# 2020.net
KiCad netlist of a schematic drawn in Altium Designer
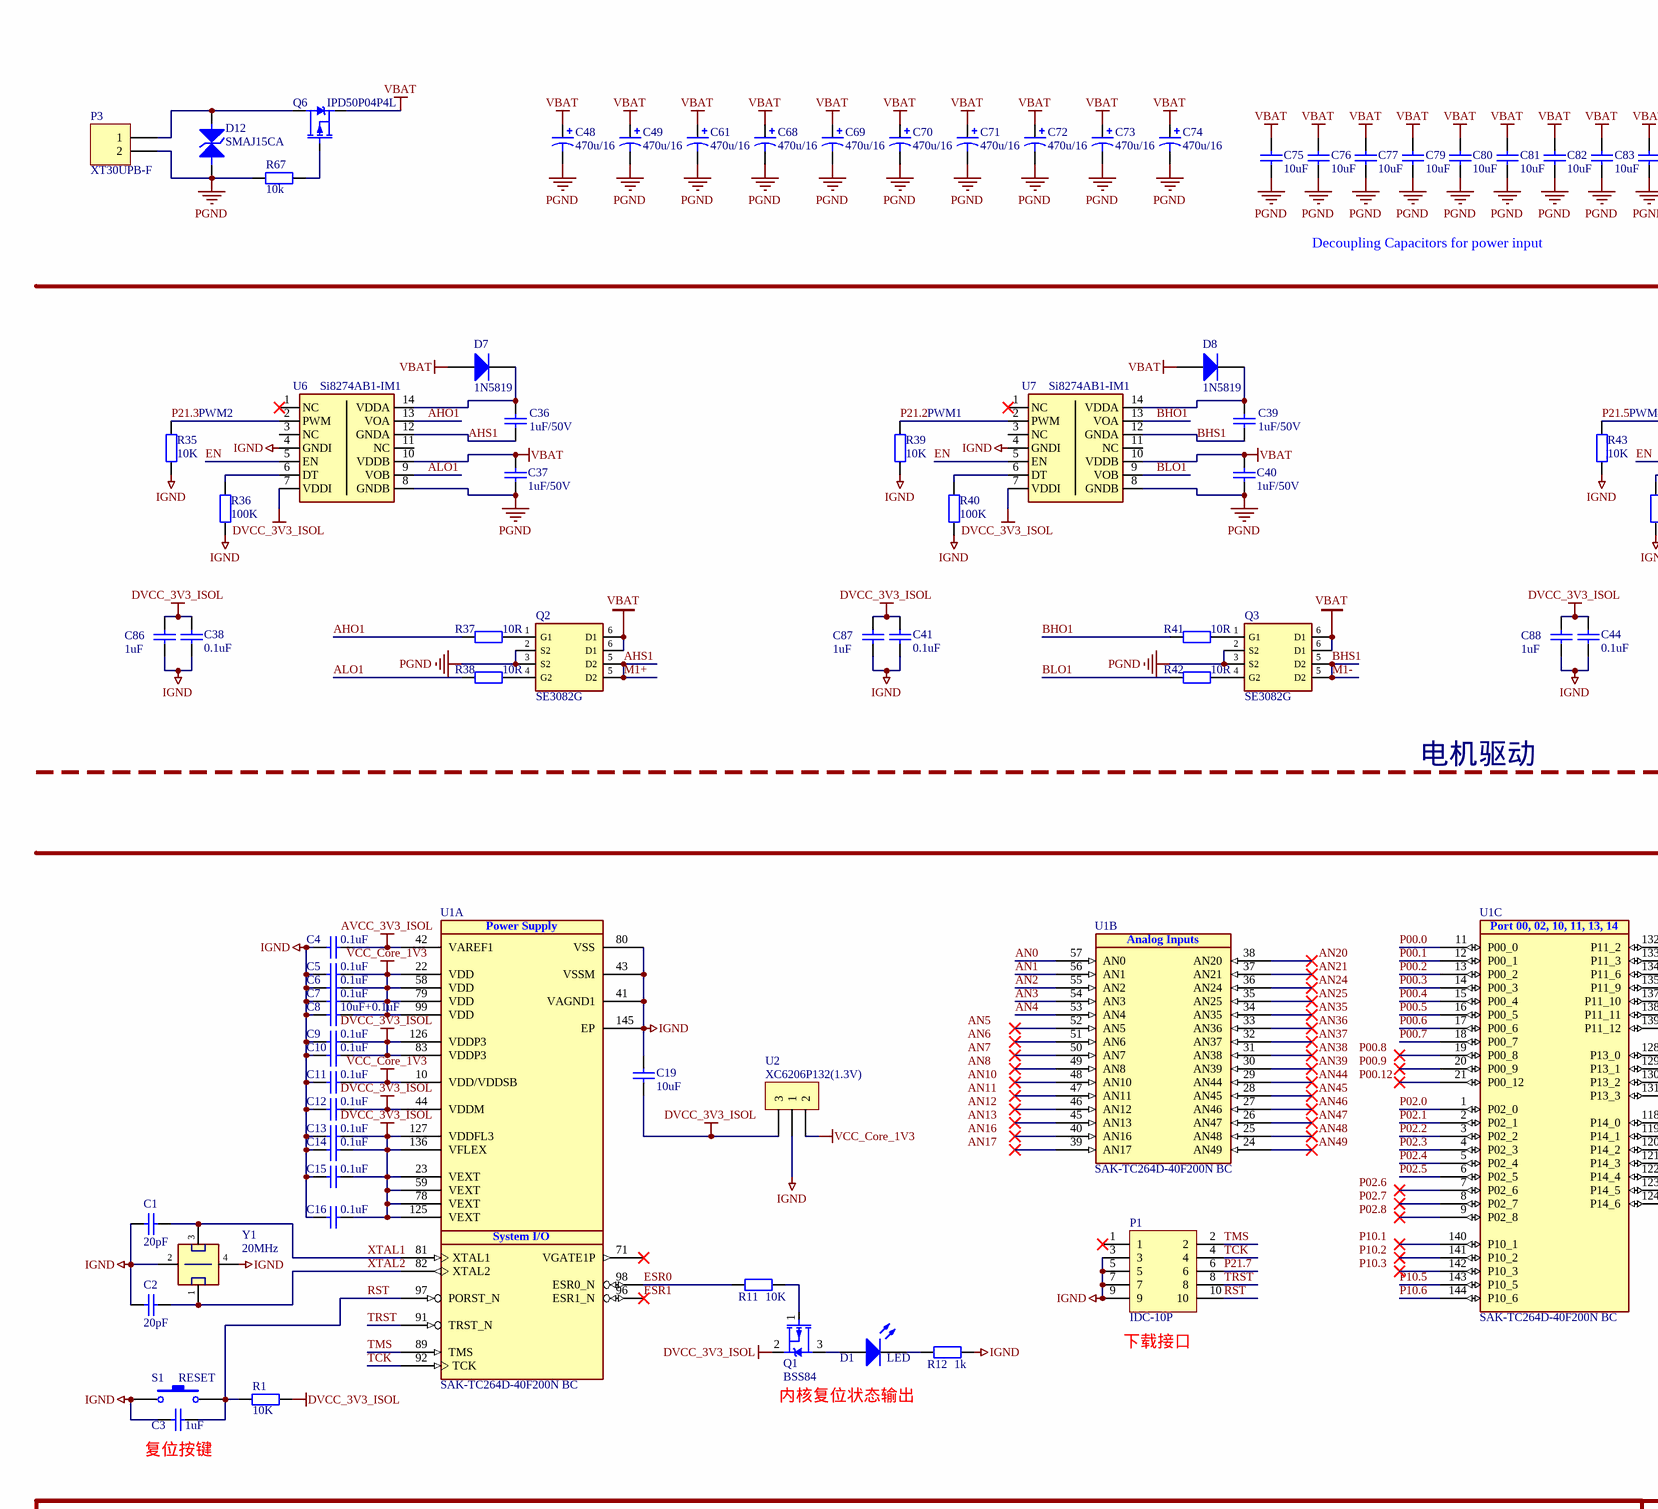
[diagram p0: 2020智能车.SchDoc, top left]
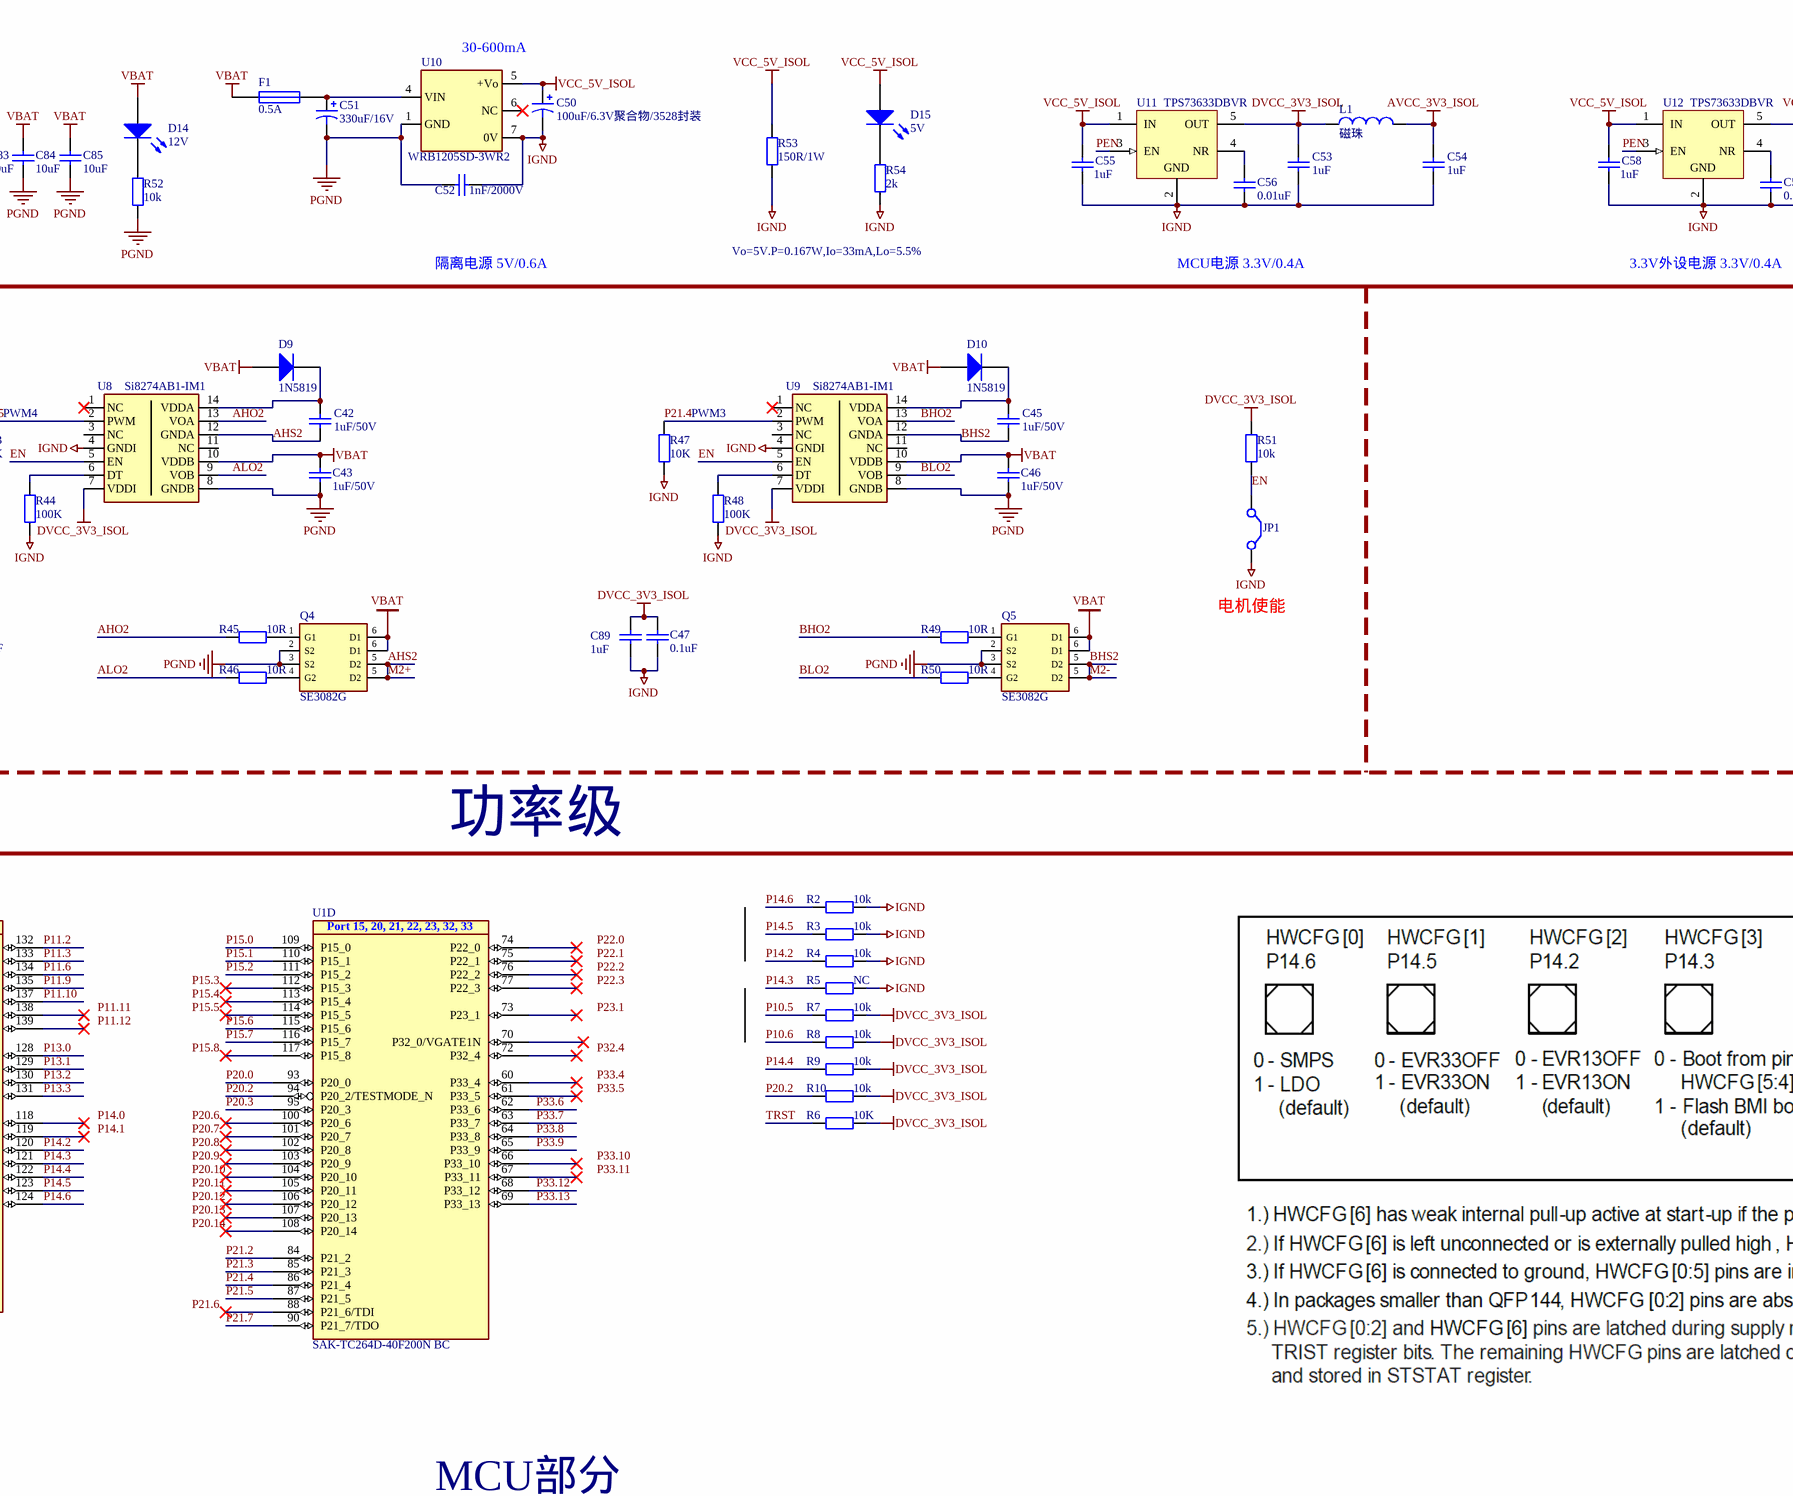
[diagram p1: 2020智能车.SchDoc, top middle]
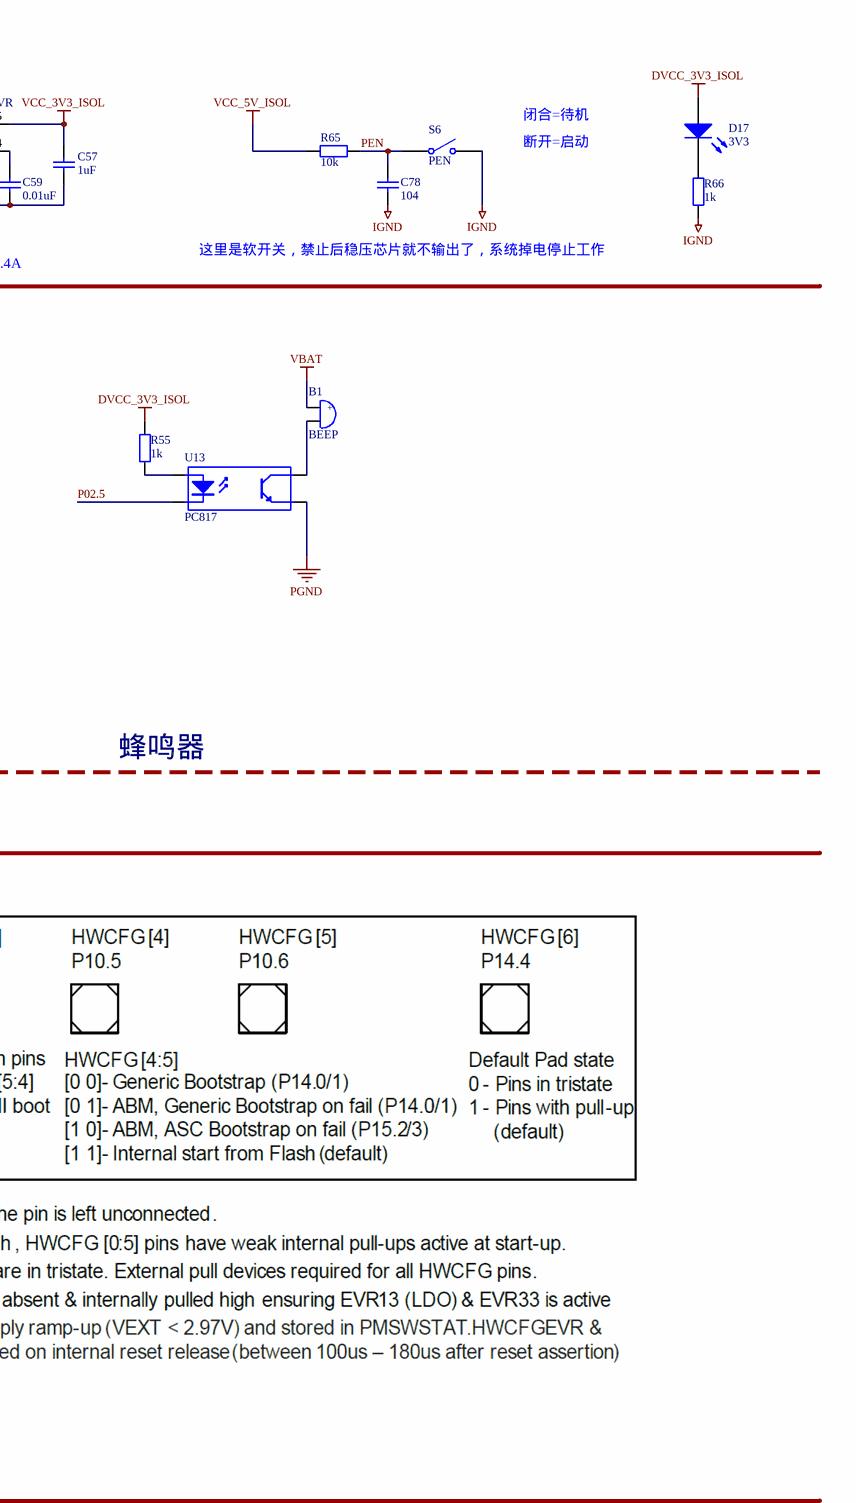
[diagram p2: 2020智能车.SchDoc, top right]
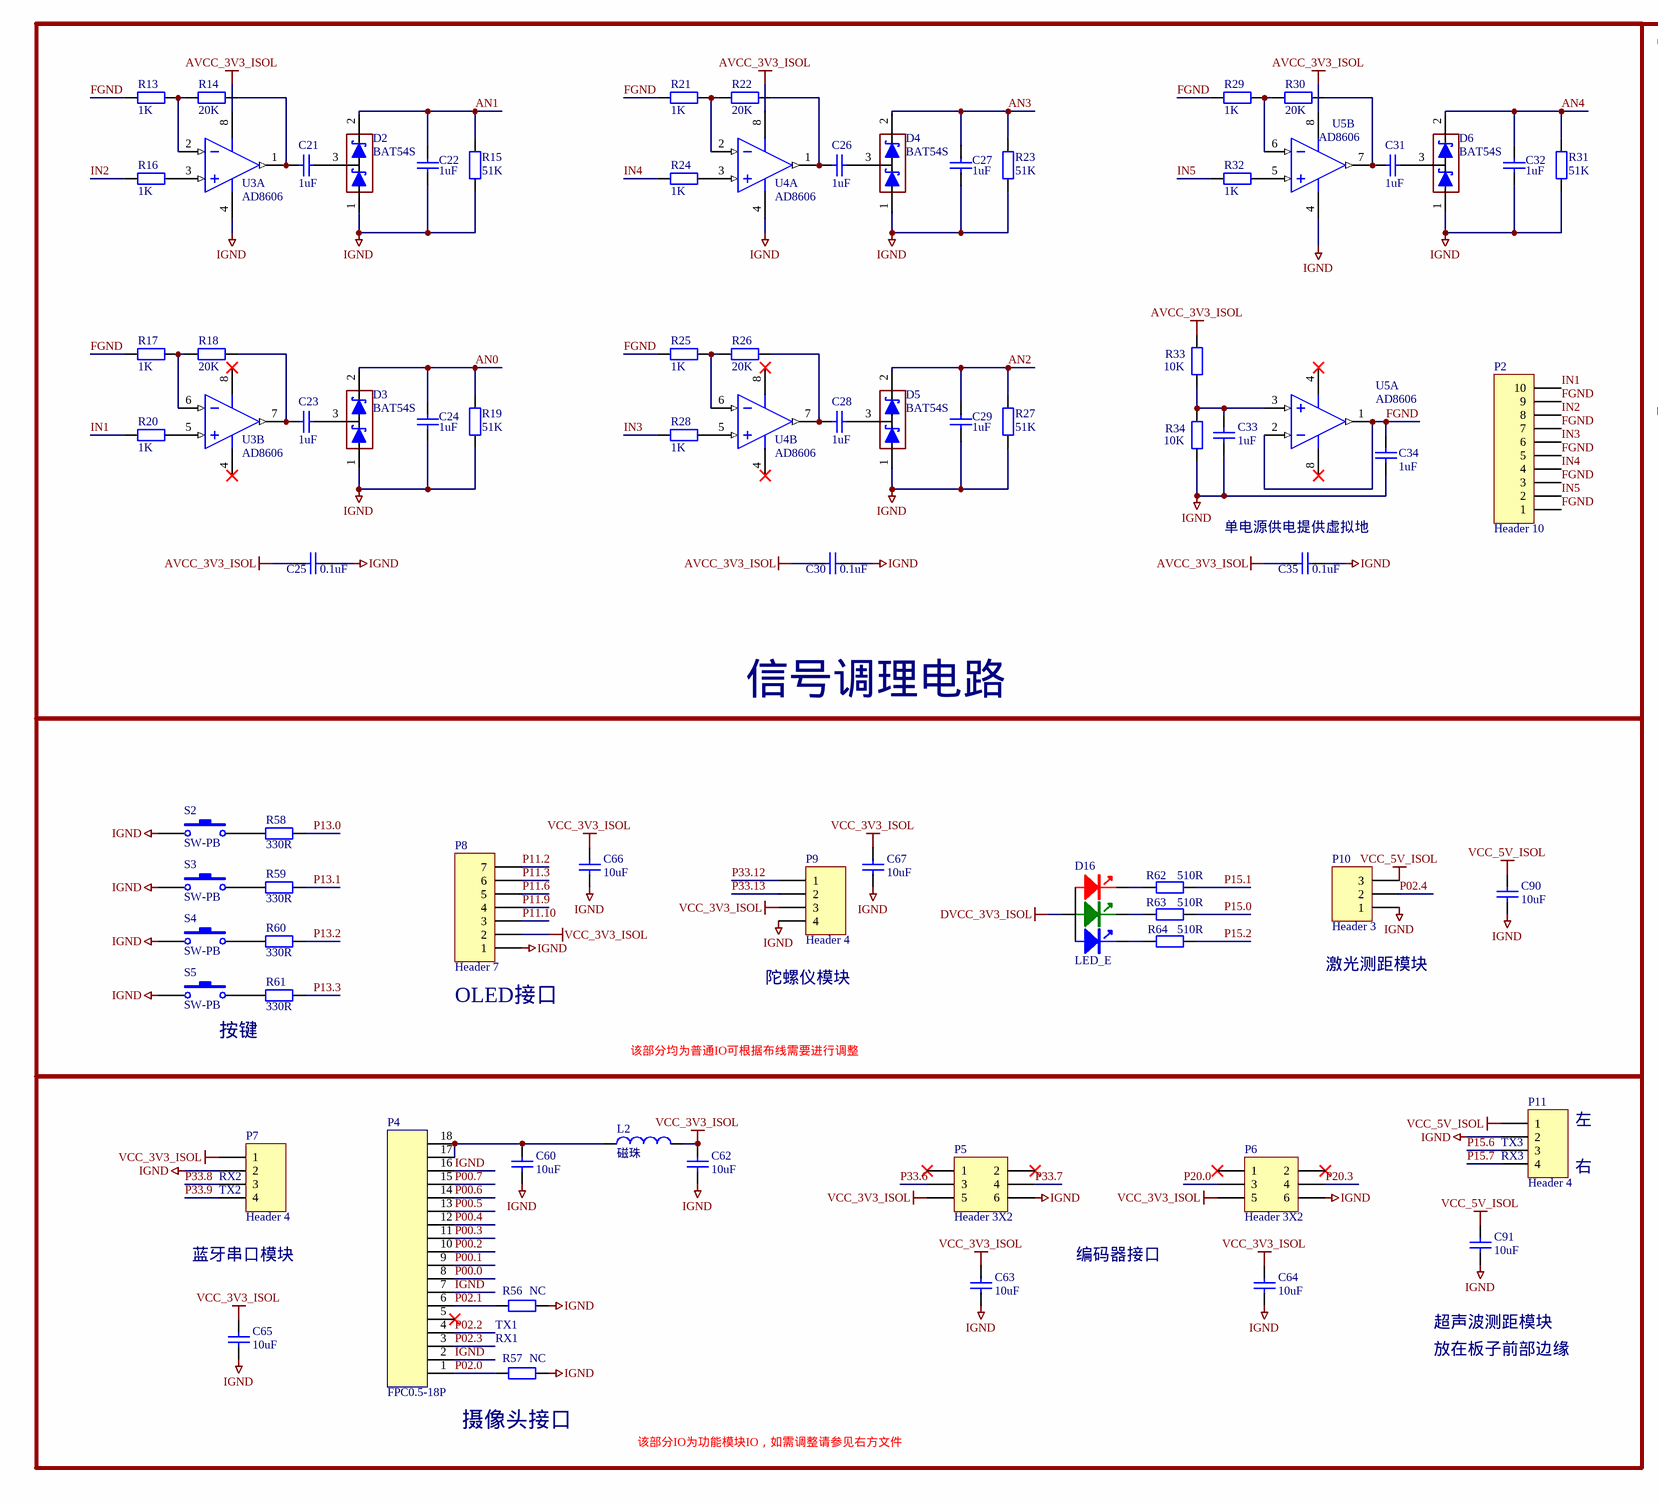
[diagram p3: 2020智能车.SchDoc, bottom left]
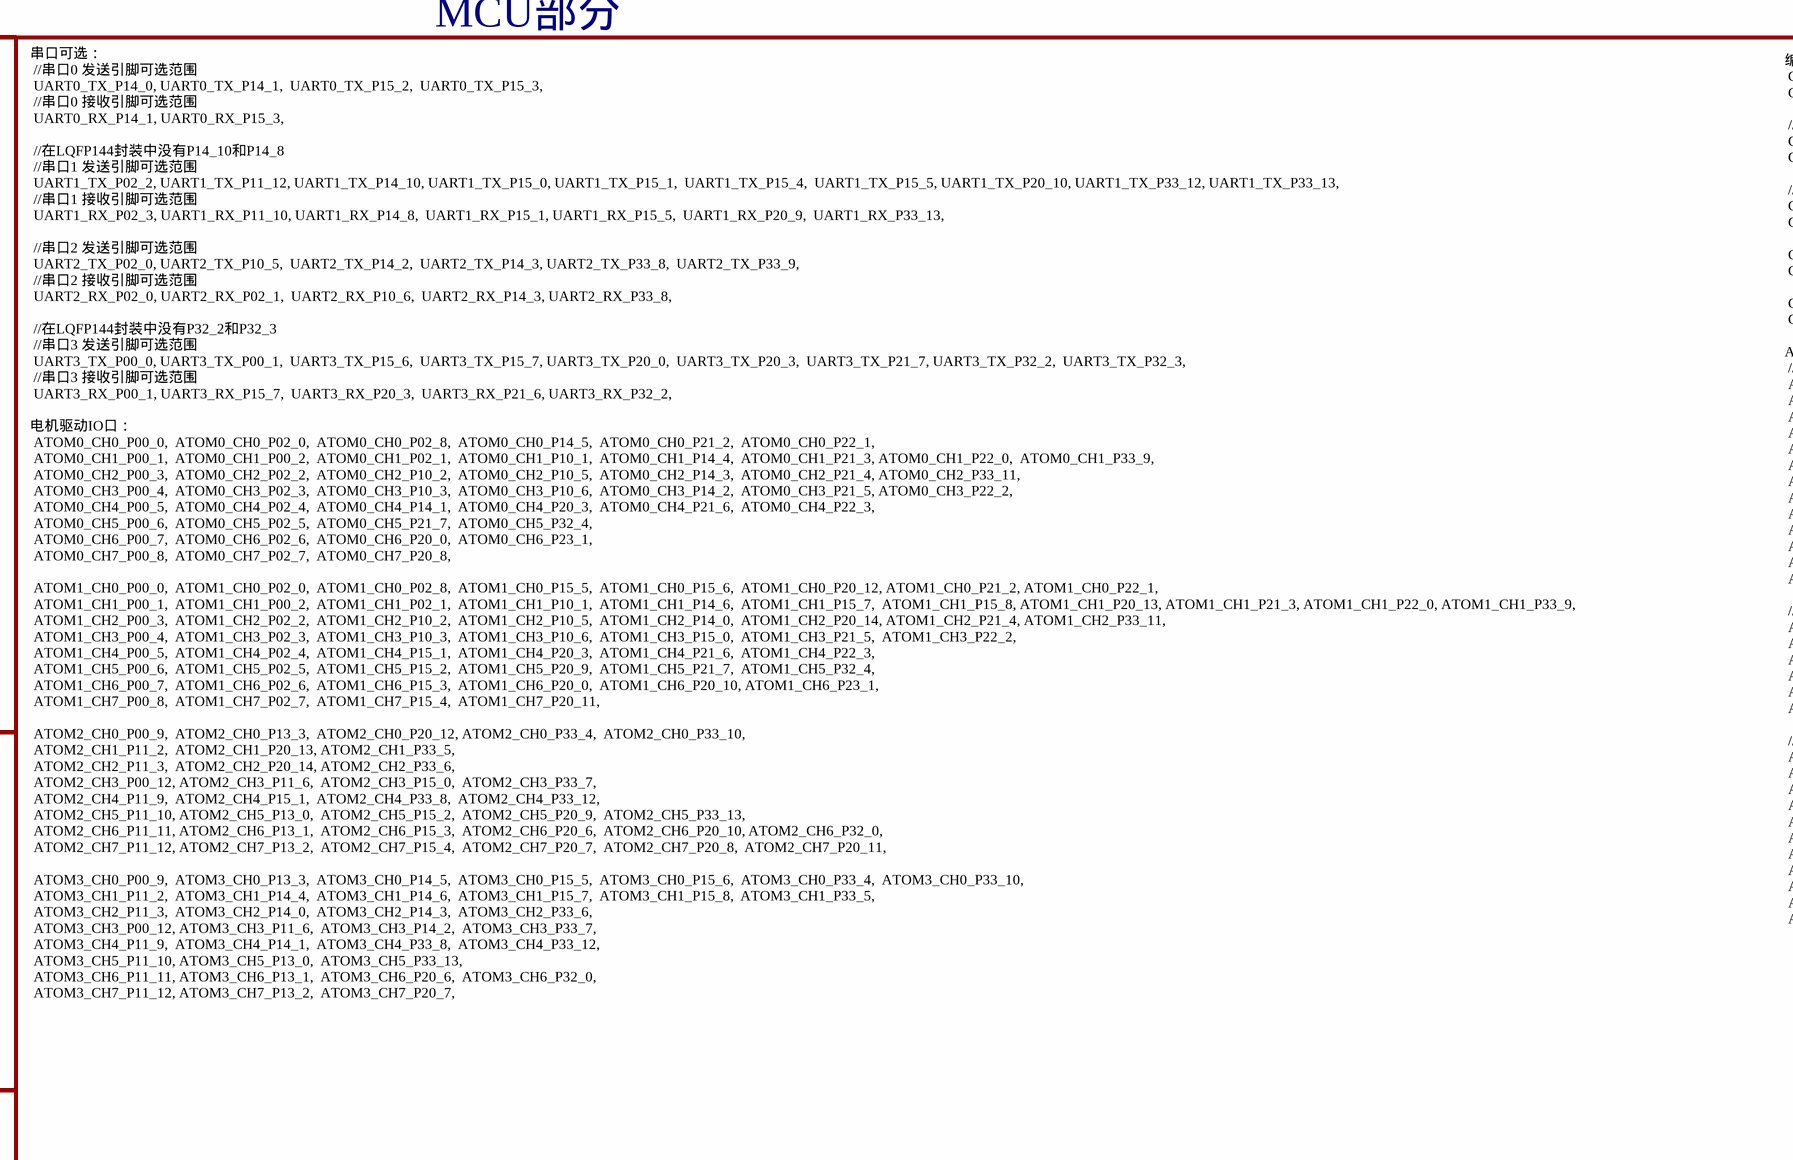
[diagram p4: 2020智能车.SchDoc, bottom middle]
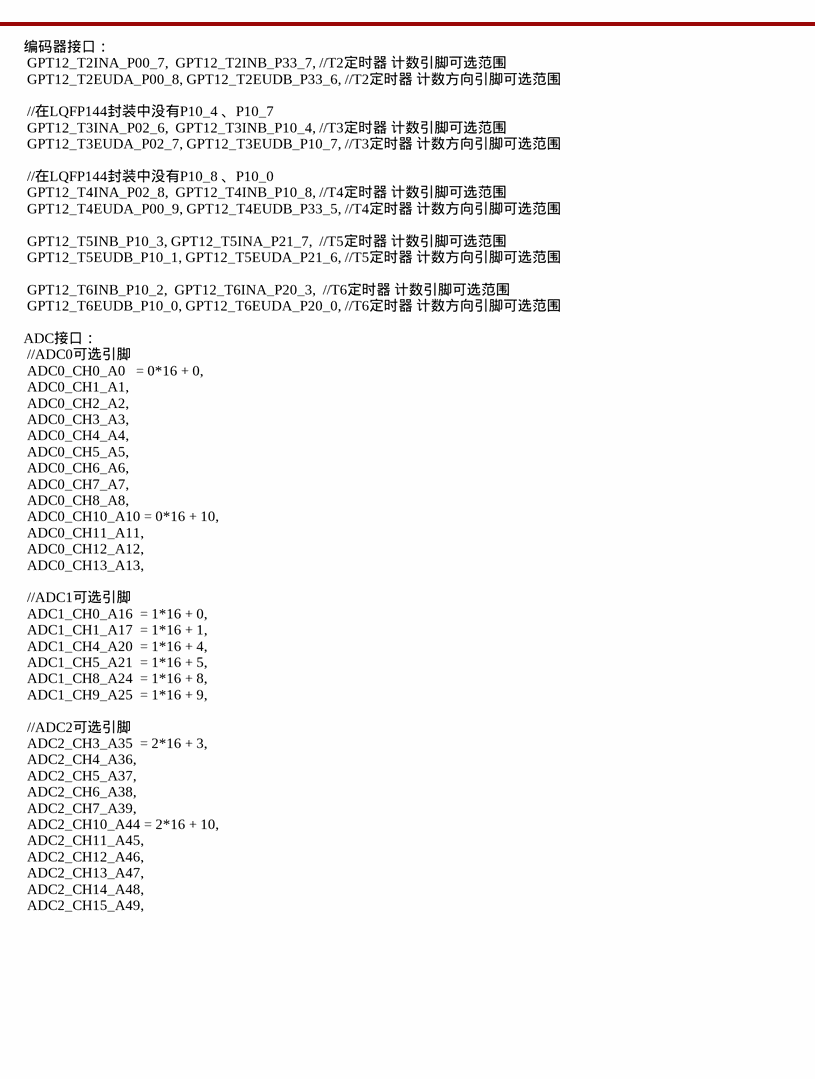
[diagram p5: 2020智能车.SchDoc, bottom right]

(export (version "E")
  (design (tool "Eeschema 10.0.6"))
  (components
    (comp (ref "B1")
      (value "BEEP")
      (footprint "E10/5")
      (description "蜂鸣器")
      (libsource (lib "蜂鸣器") (part "BEEP"))
    )
    (comp (ref "C1")
      (value "20pF")
      (footprint "0603-1")
      (description "Capacitor")
      (fields (field (name "Comment") "Cap") (field (name "PUBLISHER") "Altium Limited"))
      (libsource (lib "Miscellaneous Devices") (part "Cap"))
    )
    (comp (ref "C2")
      (value "20pF")
      (footprint "0603-1")
      (description "Capacitor")
      (fields (field (name "Comment") "Cap") (field (name "PUBLISHER") "Altium Limited"))
      (libsource (lib "Miscellaneous Devices") (part "Cap"))
    )
    (comp (ref "C3")
      (value "1uF")
      (footprint "0603-1")
      (description "Capacitor")
      (libsource (lib "Miscellaneous Devices") (part "Cap"))
    )
    (comp (ref "C4")
      (value "0.1uF")
      (footprint "0603-1")
      (description "Capacitor")
      (libsource (lib "Miscellaneous Devices") (part "Cap"))
    )
    (comp (ref "C5")
      (value "0.1uF")
      (footprint "0603-1")
      (description "Capacitor")
      (libsource (lib "Miscellaneous Devices") (part "Cap"))
    )
    (comp (ref "C6")
      (value "0.1uF")
      (footprint "0603-1")
      (description "Capacitor")
      (libsource (lib "Miscellaneous Devices") (part "Cap"))
    )
    (comp (ref "C7")
      (value "0.1uF")
      (footprint "0603-1")
      (description "Capacitor")
      (libsource (lib "Miscellaneous Devices") (part "Cap"))
    )
    (comp (ref "C8")
      (value "10uF+0.1uF")
      (footprint "0603-1")
      (description "Capacitor")
      (libsource (lib "Miscellaneous Devices") (part "Cap"))
    )
    (comp (ref "C9")
      (value "0.1uF")
      (footprint "0603-1")
      (description "Capacitor")
      (libsource (lib "Miscellaneous Devices") (part "Cap"))
    )
    (comp (ref "C10")
      (value "0.1uF")
      (footprint "0603-1")
      (description "Capacitor")
      (libsource (lib "Miscellaneous Devices") (part "Cap"))
    )
    (comp (ref "C11")
      (value "0.1uF")
      (footprint "0603-1")
      (description "Capacitor")
      (libsource (lib "Miscellaneous Devices") (part "Cap"))
    )
    (comp (ref "C12")
      (value "0.1uF")
      (footprint "0603-1")
      (description "Capacitor")
      (libsource (lib "Miscellaneous Devices") (part "Cap"))
    )
    (comp (ref "C13")
      (value "0.1uF")
      (footprint "0603-1")
      (description "Capacitor")
      (libsource (lib "Miscellaneous Devices") (part "Cap"))
    )
    (comp (ref "C14")
      (value "0.1uF")
      (footprint "0603-1")
      (description "Capacitor")
      (libsource (lib "Miscellaneous Devices") (part "Cap"))
    )
    (comp (ref "C15")
      (value "0.1uF")
      (footprint "0603-1")
      (description "Capacitor")
      (libsource (lib "Miscellaneous Devices") (part "Cap"))
    )
    (comp (ref "C16")
      (value "0.1uF")
      (footprint "0603-1")
      (description "Capacitor")
      (libsource (lib "Miscellaneous Devices") (part "Cap"))
    )
    (comp (ref "C19")
      (value "10uF")
      (footprint "0603-1")
      (description "Capacitor")
      (libsource (lib "Miscellaneous Devices") (part "Cap"))
    )
    (comp (ref "C21")
      (value "1uF")
      (footprint "0603-1")
      (description "Capacitor")
      (libsource (lib "Miscellaneous Devices") (part "Cap"))
    )
    (comp (ref "C22")
      (value "1uF")
      (footprint "0603-1")
      (description "Capacitor")
      (libsource (lib "Miscellaneous Devices") (part "Cap"))
    )
    (comp (ref "C23")
      (value "1uF")
      (footprint "0603-1")
      (description "Capacitor")
      (libsource (lib "Miscellaneous Devices") (part "Cap"))
    )
    (comp (ref "C24")
      (value "1uF")
      (footprint "0603-1")
      (description "Capacitor")
      (libsource (lib "Miscellaneous Devices") (part "Cap"))
    )
    (comp (ref "C25")
      (value "0.1uF")
      (footprint "0603-1")
      (description "Capacitor")
      (fields (field (name "PUBLISHER") "Altium Limited"))
      (libsource (lib "Miscellaneous Devices") (part "Cap"))
    )
    (comp (ref "C26")
      (value "1uF")
      (footprint "0603-1")
      (description "Capacitor")
      (libsource (lib "Miscellaneous Devices") (part "Cap"))
    )
    (comp (ref "C27")
      (value "1uF")
      (footprint "0603-1")
      (description "Capacitor")
      (libsource (lib "Miscellaneous Devices") (part "Cap"))
    )
    (comp (ref "C28")
      (value "1uF")
      (footprint "0603-1")
      (description "Capacitor")
      (libsource (lib "Miscellaneous Devices") (part "Cap"))
    )
    (comp (ref "C29")
      (value "1uF")
      (footprint "0603-1")
      (description "Capacitor")
      (libsource (lib "Miscellaneous Devices") (part "Cap"))
    )
    (comp (ref "C30")
      (value "0.1uF")
      (footprint "0603-1")
      (description "Capacitor")
      (fields (field (name "PUBLISHER") "Altium Limited"))
      (libsource (lib "Miscellaneous Devices") (part "Cap"))
    )
    (comp (ref "C31")
      (value "1uF")
      (footprint "0603-1")
      (description "Capacitor")
      (libsource (lib "Miscellaneous Devices") (part "Cap"))
    )
    (comp (ref "C32")
      (value "1uF")
      (footprint "0603-1")
      (description "Capacitor")
      (libsource (lib "Miscellaneous Devices") (part "Cap"))
    )
    (comp (ref "C33")
      (value "1uF")
      (footprint "0603-1")
      (description "Capacitor")
      (libsource (lib "Miscellaneous Devices") (part "Cap"))
    )
    (comp (ref "C34")
      (value "1uF")
      (footprint "0603-1")
      (description "Capacitor")
      (libsource (lib "Miscellaneous Devices") (part "Cap"))
    )
    (comp (ref "C35")
      (value "0.1uF")
      (footprint "0603-1")
      (description "Capacitor")
      (fields (field (name "PUBLISHER") "Altium Limited"))
      (libsource (lib "Miscellaneous Devices") (part "Cap"))
    )
    (comp (ref "C36")
      (value "1uF/50V")
      (footprint "0603-1")
      (description "Capacitor")
      (libsource (lib "Miscellaneous Devices") (part "Cap"))
    )
    (comp (ref "C37")
      (value "1uF/50V")
      (footprint "0603-1")
      (description "Capacitor")
      (libsource (lib "Miscellaneous Devices") (part "Cap"))
    )
    (comp (ref "C38")
      (value "0.1uF")
      (footprint "0603-1")
      (description "Capacitor")
      (libsource (lib "Miscellaneous Devices") (part "Cap"))
    )
    (comp (ref "C39")
      (value "1uF/50V")
      (footprint "0603-1")
      (description "Capacitor")
      (libsource (lib "Miscellaneous Devices") (part "Cap"))
    )
    (comp (ref "C40")
      (value "1uF/50V")
      (footprint "0603-1")
      (description "Capacitor")
      (libsource (lib "Miscellaneous Devices") (part "Cap"))
    )
    (comp (ref "C41")
      (value "0.1uF")
      (footprint "0603-1")
      (description "Capacitor")
      (libsource (lib "Miscellaneous Devices") (part "Cap"))
    )
    (comp (ref "C42")
      (value "1uF/50V")
      (footprint "0603-1")
      (description "Capacitor")
      (libsource (lib "Miscellaneous Devices") (part "Cap"))
    )
    (comp (ref "C43")
      (value "1uF/50V")
      (footprint "0603-1")
      (description "Capacitor")
      (libsource (lib "Miscellaneous Devices") (part "Cap"))
    )
    (comp (ref "C44")
      (value "0.1uF")
      (footprint "0603-1")
      (description "Capacitor")
      (libsource (lib "Miscellaneous Devices") (part "Cap"))
    )
    (comp (ref "C45")
      (value "1uF/50V")
      (footprint "0603-1")
      (description "Capacitor")
      (libsource (lib "Miscellaneous Devices") (part "Cap"))
    )
    (comp (ref "C46")
      (value "1uF/50V")
      (footprint "0603-1")
      (description "Capacitor")
      (libsource (lib "Miscellaneous Devices") (part "Cap"))
    )
    (comp (ref "C47")
      (value "0.1uF")
      (footprint "0603-1")
      (description "Capacitor")
      (libsource (lib "Miscellaneous Devices") (part "Cap"))
    )
    (comp (ref "C48")
      (value "470u/16")
      (footprint "E10/5")
      (description "Polarized Capacitor (Radial)")
      (libsource (lib "Miscellaneous Devices") (part "Cap Pol1"))
    )
    (comp (ref "C49")
      (value "470u/16")
      (footprint "E10/5")
      (description "Polarized Capacitor (Radial)")
      (libsource (lib "Miscellaneous Devices") (part "Cap Pol1"))
    )
    (comp (ref "C50")
      (value "100uF/6.3V聚合物/3528封装")
      (footprint "3528-B")
      (description "Polarized Capacitor (Radial)")
      (libsource (lib "Miscellaneous Devices") (part "Cap Pol1"))
    )
    (comp (ref "C51")
      (value "330uF/16V")
      (footprint "E6.5/2.5")
      (description "Polarized Capacitor (Radial)")
      (libsource (lib "Miscellaneous Devices") (part "Cap Pol1"))
    )
    (comp (ref "C52")
      (value "1nF/2000V")
      (footprint "1812")
      (description "Capacitor")
      (libsource (lib "Miscellaneous Devices") (part "Cap"))
    )
    (comp (ref "C53")
      (value "1uF")
      (footprint "0603-1")
      (description "Capacitor")
      (fields (field (name "PUBLISHER") "Altium Limited"))
      (libsource (lib "Miscellaneous Devices") (part "Cap"))
    )
    (comp (ref "C54")
      (value "1uF")
      (footprint "0603-1")
      (description "Capacitor")
      (fields (field (name "PUBLISHER") "Altium Limited"))
      (libsource (lib "Miscellaneous Devices") (part "Cap"))
    )
    (comp (ref "C55")
      (value "1uF")
      (footprint "0603-1")
      (description "Capacitor")
      (fields (field (name "PUBLISHER") "Altium Limited"))
      (libsource (lib "Miscellaneous Devices") (part "Cap"))
    )
    (comp (ref "C56")
      (value "0.01uF")
      (footprint "0603-1")
      (description "Capacitor")
      (fields (field (name "PUBLISHER") "Altium Limited"))
      (libsource (lib "Miscellaneous Devices") (part "Cap"))
    )
    (comp (ref "C57")
      (value "1uF")
      (footprint "0603-1")
      (description "Capacitor")
      (fields (field (name "PUBLISHER") "Altium Limited"))
      (libsource (lib "Miscellaneous Devices") (part "Cap"))
    )
    (comp (ref "C58")
      (value "1uF")
      (footprint "0603-1")
      (description "Capacitor")
      (fields (field (name "PUBLISHER") "Altium Limited"))
      (libsource (lib "Miscellaneous Devices") (part "Cap"))
    )
    (comp (ref "C59")
      (value "0.01uF")
      (footprint "0603-1")
      (description "Capacitor")
      (fields (field (name "PUBLISHER") "Altium Limited"))
      (libsource (lib "Miscellaneous Devices") (part "Cap"))
    )
    (comp (ref "C60")
      (value "10uF")
      (footprint "0603-1")
      (description "Capacitor")
      (libsource (lib "Miscellaneous Devices") (part "Cap"))
    )
    (comp (ref "C61")
      (value "470u/16")
      (footprint "E10/5")
      (description "Polarized Capacitor (Radial)")
      (libsource (lib "Miscellaneous Devices") (part "Cap Pol1"))
    )
    (comp (ref "C62")
      (value "10uF")
      (footprint "0603-1")
      (description "Capacitor")
      (libsource (lib "Miscellaneous Devices") (part "Cap"))
    )
    (comp (ref "C63")
      (value "10uF")
      (footprint "0805-3")
      (description "Capacitor")
      (libsource (lib "Miscellaneous Devices") (part "Cap"))
    )
    (comp (ref "C64")
      (value "10uF")
      (footprint "0805-3")
      (description "Capacitor")
      (libsource (lib "Miscellaneous Devices") (part "Cap"))
    )
    (comp (ref "C65")
      (value "10uF")
      (footprint "0603-1")
      (description "Capacitor")
      (libsource (lib "Miscellaneous Devices") (part "Cap"))
    )
    (comp (ref "C66")
      (value "10uF")
      (footprint "0603-1")
      (description "Capacitor")
      (libsource (lib "Miscellaneous Devices") (part "Cap"))
    )
    (comp (ref "C67")
      (value "10uF")
      (footprint "0603-1")
      (description "Capacitor")
      (libsource (lib "Miscellaneous Devices") (part "Cap"))
    )
    (comp (ref "C68")
      (value "470u/16")
      (footprint "E10/5")
      (description "Polarized Capacitor (Radial)")
      (libsource (lib "Miscellaneous Devices") (part "Cap Pol1"))
    )
    (comp (ref "C69")
      (value "470u/16")
      (footprint "E10/5")
      (description "Polarized Capacitor (Radial)")
      (libsource (lib "Miscellaneous Devices") (part "Cap Pol1"))
    )
    (comp (ref "C70")
      (value "470u/16")
      (footprint "E10/5")
      (description "Polarized Capacitor (Radial)")
      (libsource (lib "Miscellaneous Devices") (part "Cap Pol1"))
    )
    (comp (ref "C71")
      (value "470u/16")
      (footprint "E10/5")
      (description "Polarized Capacitor (Radial)")
      (libsource (lib "Miscellaneous Devices") (part "Cap Pol1"))
    )
    (comp (ref "C72")
      (value "470u/16")
      (footprint "E10/5")
      (description "Polarized Capacitor (Radial)")
      (libsource (lib "Miscellaneous Devices") (part "Cap Pol1"))
    )
    (comp (ref "C73")
      (value "470u/16")
      (footprint "E10/5")
      (description "Polarized Capacitor (Radial)")
      (libsource (lib "Miscellaneous Devices") (part "Cap Pol1"))
    )
    (comp (ref "C74")
      (value "470u/16")
      (footprint "E10/5")
      (description "Polarized Capacitor (Radial)")
      (libsource (lib "Miscellaneous Devices") (part "Cap Pol1"))
    )
    (comp (ref "C75")
      (value "10uF")
      (footprint "3528-B")
      (description "Capacitor")
      (libsource (lib "Miscellaneous Devices") (part "Cap"))
    )
    (comp (ref "C76")
      (value "10uF")
      (footprint "3528-B")
      (description "Capacitor")
      (libsource (lib "Miscellaneous Devices") (part "Cap"))
    )
    (comp (ref "C77")
      (value "10uF")
      (footprint "3528-B")
      (description "Capacitor")
      (libsource (lib "Miscellaneous Devices") (part "Cap"))
    )
    (comp (ref "C78")
      (value "104")
      (footprint "0603-1")
      (description "Capacitor")
      (fields (field (name "PUBLISHER") "Altium Limited"))
      (libsource (lib "Miscellaneous Devices") (part "Cap"))
    )
    (comp (ref "C79")
      (value "10uF")
      (footprint "3528-B")
      (description "Capacitor")
      (libsource (lib "Miscellaneous Devices") (part "Cap"))
    )
    (comp (ref "C80")
      (value "10uF")
      (footprint "3528-B")
      (description "Capacitor")
      (libsource (lib "Miscellaneous Devices") (part "Cap"))
    )
    (comp (ref "C81")
      (value "10uF")
      (footprint "3528-B")
      (description "Capacitor")
      (libsource (lib "Miscellaneous Devices") (part "Cap"))
    )
    (comp (ref "C82")
      (value "10uF")
      (footprint "3528-B")
      (description "Capacitor")
      (libsource (lib "Miscellaneous Devices") (part "Cap"))
    )
    (comp (ref "C83")
      (value "10uF")
      (footprint "3528-B")
      (description "Capacitor")
      (libsource (lib "Miscellaneous Devices") (part "Cap"))
    )
    (comp (ref "C84")
      (value "10uF")
      (footprint "3528-B")
      (description "Capacitor")
      (libsource (lib "Miscellaneous Devices") (part "Cap"))
    )
    (comp (ref "C85")
      (value "10uF")
      (footprint "3528-B")
      (description "Capacitor")
      (libsource (lib "Miscellaneous Devices") (part "Cap"))
    )
    (comp (ref "C86")
      (value "1uF")
      (footprint "0603-1")
      (description "Capacitor")
      (libsource (lib "Miscellaneous Devices") (part "Cap"))
    )
    (comp (ref "C87")
      (value "1uF")
      (footprint "0603-1")
      (description "Capacitor")
      (libsource (lib "Miscellaneous Devices") (part "Cap"))
    )
    (comp (ref "C88")
      (value "1uF")
      (footprint "0603-1")
      (description "Capacitor")
      (libsource (lib "Miscellaneous Devices") (part "Cap"))
    )
    (comp (ref "C89")
      (value "1uF")
      (footprint "0603-1")
      (description "Capacitor")
      (libsource (lib "Miscellaneous Devices") (part "Cap"))
    )
    (comp (ref "C90")
      (value "10uF")
      (footprint "0603-1")
      (description "Capacitor")
      (libsource (lib "Miscellaneous Devices") (part "Cap"))
    )
    (comp (ref "C91")
      (value "10uF")
      (footprint "0603-1")
      (description "Capacitor")
      (libsource (lib "Miscellaneous Devices") (part "Cap"))
    )
    (comp (ref "D1")
      (value "LED")
      (footprint "0603-3")
      (description "Typical INFRARED GaAs LED")
      (libsource (lib "Miscellaneous Devices") (part "LED0"))
    )
    (comp (ref "D2") (value "BAT54S") (footprint "SOT-23-3") (libsource (lib "my_library") (part "BAT54S")))
    (comp (ref "D3") (value "BAT54S") (footprint "SOT-23-3") (libsource (lib "my_library") (part "BAT54S")))
    (comp (ref "D4") (value "BAT54S") (footprint "SOT-23-3") (libsource (lib "my_library") (part "BAT54S")))
    (comp (ref "D5") (value "BAT54S") (footprint "SOT-23-3") (libsource (lib "my_library") (part "BAT54S")))
    (comp (ref "D6") (value "BAT54S") (footprint "SOT-23-3") (libsource (lib "my_library") (part "BAT54S")))
    (comp (ref "D7")
      (value "1N5819")
      (footprint "3216-A")
      (description "Default Diode")
      (fields (field (name "PUBLISHER") "Altium Limited"))
      (libsource (lib "Miscellaneous Devices") (part "Diode"))
    )
    (comp (ref "D8")
      (value "1N5819")
      (footprint "3216-A")
      (description "Default Diode")
      (fields (field (name "PUBLISHER") "Altium Limited"))
      (libsource (lib "Miscellaneous Devices") (part "Diode"))
    )
    (comp (ref "D9")
      (value "1N5819")
      (footprint "3216-A")
      (description "Default Diode")
      (fields (field (name "PUBLISHER") "Altium Limited"))
      (libsource (lib "Miscellaneous Devices") (part "Diode"))
    )
    (comp (ref "D10")
      (value "1N5819")
      (footprint "3216-A")
      (description "Default Diode")
      (fields (field (name "PUBLISHER") "Altium Limited"))
      (libsource (lib "Miscellaneous Devices") (part "Diode"))
    )
    (comp (ref "D12")
      (value "SMAJ15CA")
      (footprint "6032-C")
      (description "双向瞬态抑制二极管")
      (libsource (lib "二极管") (part "TVS"))
    )
    (comp (ref "D14")
      (value "12V")
      (footprint "0603-3")
      (description "Typical INFRARED GaAs LED")
      (libsource (lib "Miscellaneous Devices") (part "LED0"))
    )
    (comp (ref "D15")
      (value "5V")
      (footprint "0603-3")
      (description "Typical INFRARED GaAs LED")
      (libsource (lib "Miscellaneous Devices") (part "LED0"))
    )
    (comp (ref "D16") (value "LED_E") (footprint "1210-DLED") (libsource (lib "MySchLib") (part "LED_E")))
    (comp (ref "D17")
      (value "3V3")
      (footprint "0603-3")
      (description "Typical INFRARED GaAs LED")
      (libsource (lib "Miscellaneous Devices") (part "LED0"))
    )
    (comp (ref "F1")
      (value "0.5A")
      (footprint "1812")
      (description "Fuse")
      (fields (field (name "PUBLISHER") "Altium Limited"))
      (libsource (lib "Miscellaneous Devices") (part "Fuse 1"))
    )
    (comp (ref "JP1")
      (value "Jumper")
      (footprint "CON-2S")
      (description "Jumper Wire")
      (fields (field (name "PUBLISHER") "Altium Limited"))
      (libsource (lib "Miscellaneous Devices") (part "Jumper"))
    )
    (comp (ref "L1")
      (value "磁珠")
      (footprint "0805-3")
      (description "Inductor")
      (libsource (lib "Miscellaneous Devices") (part "Inductor"))
    )
    (comp (ref "L2")
      (value "磁珠")
      (footprint "0805-3")
      (description "Inductor")
      (libsource (lib "Miscellaneous Devices") (part "Inductor"))
    )
    (comp (ref "P1") (value "IDC-10P") (footprint "MHDR2X5") (libsource (lib "简易牛角座") (part "IDC-10P")))
    (comp (ref "P2")
      (value "Header 10")
      (footprint "MX 1.25-WS-10P")
      (description "Header, 10-Pin")
      (fields (field (name "PUBLISHER") "Altium Limited"))
      (libsource (lib "Miscellaneous Connectors") (part "Header 10"))
    )
    (comp (ref "P3")
      (value "XT30UPB-F")
      (footprint "XT30UPB-F")
      (description "Header, 2-Pin")
      (fields (field (name "PUBLISHER") "Altium Limited"))
      (libsource (lib "Miscellaneous Connectors") (part "Header 2"))
    )
    (comp (ref "P4")
      (value "FPC0.5-18P")
      (footprint "FPC18-0.5")
      (description "贴片")
      (libsource (lib "FPC") (part "FPC0.5-18P"))
    )
    (comp (ref "P5")
      (value "Header 3X2")
      (footprint "con-6D")
      (description "Header, 3-Pin, Dual row")
      (fields (field (name "PUBLISHER") "Altium Limited"))
      (libsource (lib "Miscellaneous Connectors") (part "Header 3X2"))
    )
    (comp (ref "P6")
      (value "Header 3X2")
      (footprint "con-6D")
      (description "Header, 3-Pin, Dual row")
      (fields (field (name "PUBLISHER") "Altium Limited"))
      (libsource (lib "Miscellaneous Connectors") (part "Header 3X2"))
    )
    (comp (ref "P7")
      (value "Header 4")
      (footprint "con-4s")
      (description "Header, 4-Pin")
      (fields (field (name "PUBLISHER") "Altium Limited"))
      (libsource (lib "Miscellaneous Connectors") (part "Header 4"))
    )
    (comp (ref "P8")
      (value "Header 7")
      (footprint "con-7s")
      (description "Header, 7-Pin")
      (fields (field (name "PUBLISHER") "Altium Limited"))
      (libsource (lib "Miscellaneous Connectors") (part "Header 7"))
    )
    (comp (ref "P9")
      (value "Header 4")
      (footprint "con-4S")
      (description "Header, 4-Pin")
      (fields (field (name "PUBLISHER") "Altium Limited"))
      (libsource (lib "Miscellaneous Connectors") (part "Header 4"))
    )
    (comp (ref "P10")
      (value "Header 3")
      (footprint "CON-3S")
      (description "Header, 3-Pin")
      (fields (field (name "PUBLISHER") "Altium Limited"))
      (libsource (lib "Miscellaneous Connectors") (part "Header 3"))
    )
    (comp (ref "P11")
      (value "Header 4")
      (footprint "CON-4S")
      (description "Header, 4-Pin")
      (fields (field (name "PUBLISHER") "Altium Limited"))
      (libsource (lib "Miscellaneous Connectors") (part "Header 4"))
    )
    (comp (ref "Q1")
      (value "BSS84")
      (footprint "SOT-23-3")
      (description "P沟道场效应管")
      (libsource (lib "") (part "P-MOS_1"))
    )
    (comp (ref "Q2")
      (value "SE3082G")
      (footprint "DFN-8_L5.5-W5.2-P1.27-LS6.0-BL-EP2")
      (libsource (lib "my_library") (part "SE3082G"))
    )
    (comp (ref "Q3")
      (value "SE3082G")
      (footprint "DFN-8_L5.5-W5.2-P1.27-LS6.0-BL-EP2")
      (libsource (lib "my_library") (part "SE3082G"))
    )
    (comp (ref "Q4")
      (value "SE3082G")
      (footprint "DFN-8_L5.5-W5.2-P1.27-LS6.0-BL-EP2")
      (libsource (lib "my_library") (part "SE3082G"))
    )
    (comp (ref "Q5")
      (value "SE3082G")
      (footprint "DFN-8_L5.5-W5.2-P1.27-LS6.0-BL-EP2")
      (libsource (lib "my_library") (part "SE3082G"))
    )
    (comp (ref "Q6")
      (value "IPD50P04P4L")
      (footprint "TO-252")
      (description "P沟道场效应管")
      (libsource (lib "MOS管") (part "P-MOS"))
    )
    (comp (ref "R1")
      (value "10K")
      (footprint "0603-1")
      (description "Resistor")
      (libsource (lib "Miscellaneous Devices") (part "Res2"))
    )
    (comp (ref "R2")
      (value "10k")
      (footprint "0603-1")
      (description "Resistor")
      (libsource (lib "Miscellaneous Devices") (part "Res2"))
    )
    (comp (ref "R3")
      (value "10k")
      (footprint "0603-1")
      (description "Resistor")
      (libsource (lib "Miscellaneous Devices") (part "Res2"))
    )
    (comp (ref "R4")
      (value "10k")
      (footprint "0603-1")
      (description "Resistor")
      (libsource (lib "Miscellaneous Devices") (part "Res2"))
    )
    (comp (ref "R5")
      (value "NC")
      (footprint "0603-1")
      (description "Resistor")
      (libsource (lib "Miscellaneous Devices") (part "Res2"))
    )
    (comp (ref "R6")
      (value "10K")
      (footprint "0603-1")
      (description "Resistor")
      (libsource (lib "Miscellaneous Devices") (part "Res2"))
    )
    (comp (ref "R7")
      (value "10k")
      (footprint "0603-1")
      (description "Resistor")
      (libsource (lib "Miscellaneous Devices") (part "Res2"))
    )
    (comp (ref "R8")
      (value "10k")
      (footprint "0603-1")
      (description "Resistor")
      (libsource (lib "Miscellaneous Devices") (part "Res2"))
    )
    (comp (ref "R9")
      (value "10k")
      (footprint "0603-1")
      (description "Resistor")
      (libsource (lib "Miscellaneous Devices") (part "Res2"))
    )
    (comp (ref "R10")
      (value "10k")
      (footprint "0603-1")
      (description "Resistor")
      (libsource (lib "Miscellaneous Devices") (part "Res2"))
    )
    (comp (ref "R11")
      (value "10K")
      (footprint "0603-1")
      (description "Resistor")
      (libsource (lib "Miscellaneous Devices") (part "Res2"))
    )
    (comp (ref "R12")
      (value "1k")
      (footprint "0603-1")
      (description "Resistor")
      (libsource (lib "Miscellaneous Devices") (part "Res2"))
    )
    (comp (ref "R13")
      (value "1K")
      (footprint "0603-1")
      (description "Resistor")
      (libsource (lib "") (part "Res2_1"))
    )
    (comp (ref "R14")
      (value "20K")
      (footprint "0603-1")
      (description "Resistor")
      (libsource (lib "") (part "Res2_1"))
    )
    (comp (ref "R15")
      (value "51K")
      (footprint "0603-1")
      (description "Resistor")
      (libsource (lib "") (part "Res2_2"))
    )
    (comp (ref "R16")
      (value "1K")
      (footprint "0603-1")
      (description "Resistor")
      (libsource (lib "") (part "Res2_1"))
    )
    (comp (ref "R17")
      (value "1K")
      (footprint "0603-1")
      (description "Resistor")
      (libsource (lib "") (part "Res2_1"))
    )
    (comp (ref "R18")
      (value "20K")
      (footprint "0603-1")
      (description "Resistor")
      (libsource (lib "") (part "Res2_1"))
    )
    (comp (ref "R19")
      (value "51K")
      (footprint "0603-1")
      (description "Resistor")
      (libsource (lib "") (part "Res2_2"))
    )
    (comp (ref "R20")
      (value "1K")
      (footprint "0603-1")
      (description "Resistor")
      (libsource (lib "") (part "Res2_1"))
    )
    (comp (ref "R21")
      (value "1K")
      (footprint "0603-1")
      (description "Resistor")
      (libsource (lib "") (part "Res2_1"))
    )
    (comp (ref "R22")
      (value "20K")
      (footprint "0603-1")
      (description "Resistor")
      (libsource (lib "") (part "Res2_1"))
    )
    (comp (ref "R23")
      (value "51K")
      (footprint "0603-1")
      (description "Resistor")
      (libsource (lib "") (part "Res2_2"))
    )
    (comp (ref "R24")
      (value "1K")
      (footprint "0603-1")
      (description "Resistor")
      (libsource (lib "") (part "Res2_1"))
    )
    (comp (ref "R25")
      (value "1K")
      (footprint "0603-1")
      (description "Resistor")
      (libsource (lib "") (part "Res2_1"))
    )
    (comp (ref "R26")
      (value "20K")
      (footprint "0603-1")
      (description "Resistor")
      (libsource (lib "") (part "Res2_1"))
    )
    (comp (ref "R27")
      (value "51K")
      (footprint "0603-1")
      (description "Resistor")
      (libsource (lib "") (part "Res2_2"))
    )
    (comp (ref "R28")
      (value "1K")
      (footprint "0603-1")
      (description "Resistor")
      (libsource (lib "") (part "Res2_1"))
    )
    (comp (ref "R29")
      (value "1K")
      (footprint "0603-1")
      (description "Resistor")
      (libsource (lib "") (part "Res2_1"))
    )
    (comp (ref "R30")
      (value "20K")
      (footprint "0603-1")
      (description "Resistor")
      (libsource (lib "") (part "Res2_1"))
    )
    (comp (ref "R31")
      (value "51K")
      (footprint "0603-1")
      (description "Resistor")
      (libsource (lib "") (part "Res2_2"))
    )
    (comp (ref "R32")
      (value "1K")
      (footprint "0603-1")
      (description "Resistor")
      (libsource (lib "") (part "Res2_1"))
    )
    (comp (ref "R33")
      (value "10K")
      (footprint "0603-1")
      (description "Resistor")
      (libsource (lib "") (part "Res2_2"))
    )
    (comp (ref "R34")
      (value "10K")
      (footprint "0603-1")
      (description "Resistor")
      (libsource (lib "") (part "Res2_2"))
    )
    (comp (ref "R35")
      (value "10K")
      (footprint "0603-1")
      (description "Resistor")
      (fields (field (name "PUBLISHER") "Altium Limited"))
      (libsource (lib "") (part "Res2_3"))
    )
    (comp (ref "R36")
      (value "100K")
      (footprint "0603-1")
      (description "Resistor")
      (fields (field (name "PUBLISHER") "Altium Limited"))
      (libsource (lib "") (part "Res2_3"))
    )
    (comp (ref "R37")
      (value "10R")
      (footprint "0603-1")
      (description "Resistor")
      (fields (field (name "PUBLISHER") "Altium Limited"))
      (libsource (lib "") (part "Res2_1"))
    )
    (comp (ref "R38")
      (value "10R")
      (footprint "0603-1")
      (description "Resistor")
      (fields (field (name "PUBLISHER") "Altium Limited"))
      (libsource (lib "") (part "Res2_1"))
    )
    (comp (ref "R39")
      (value "10K")
      (footprint "0603-1")
      (description "Resistor")
      (fields (field (name "PUBLISHER") "Altium Limited"))
      (libsource (lib "") (part "Res2_3"))
    )
    (comp (ref "R40")
      (value "100K")
      (footprint "0603-1")
      (description "Resistor")
      (fields (field (name "PUBLISHER") "Altium Limited"))
      (libsource (lib "") (part "Res2_3"))
    )
    (comp (ref "R41")
      (value "10R")
      (footprint "0603-1")
      (description "Resistor")
      (fields (field (name "PUBLISHER") "Altium Limited"))
      (libsource (lib "") (part "Res2_1"))
    )
    (comp (ref "R42")
      (value "10R")
      (footprint "0603-1")
      (description "Resistor")
      (fields (field (name "PUBLISHER") "Altium Limited"))
      (libsource (lib "") (part "Res2_1"))
    )
    (comp (ref "R43")
      (value "10K")
      (footprint "0603-1")
      (description "Resistor")
      (fields (field (name "PUBLISHER") "Altium Limited"))
      (libsource (lib "") (part "Res2_3"))
    )
    (comp (ref "R44")
      (value "100K")
      (footprint "0603-1")
      (description "Resistor")
      (fields (field (name "PUBLISHER") "Altium Limited"))
      (libsource (lib "") (part "Res2_3"))
    )
    (comp (ref "R45")
      (value "10R")
      (footprint "0603-1")
      (description "Resistor")
      (fields (field (name "PUBLISHER") "Altium Limited"))
      (libsource (lib "") (part "Res2_1"))
    )
    (comp (ref "R46")
      (value "10R")
      (footprint "0603-1")
      (description "Resistor")
      (fields (field (name "PUBLISHER") "Altium Limited"))
      (libsource (lib "") (part "Res2_1"))
    )
    (comp (ref "R47")
      (value "10K")
      (footprint "0603-1")
      (description "Resistor")
      (fields (field (name "PUBLISHER") "Altium Limited"))
      (libsource (lib "") (part "Res2_3"))
    )
    (comp (ref "R48")
      (value "100K")
      (footprint "0603-1")
      (description "Resistor")
      (fields (field (name "PUBLISHER") "Altium Limited"))
      (libsource (lib "") (part "Res2_3"))
    )
    (comp (ref "R49")
      (value "10R")
      (footprint "0603-1")
      (description "Resistor")
      (fields (field (name "PUBLISHER") "Altium Limited"))
      (libsource (lib "") (part "Res2_1"))
    )
    (comp (ref "R50")
      (value "10R")
      (footprint "0603-1")
      (description "Resistor")
      (fields (field (name "PUBLISHER") "Altium Limited"))
      (libsource (lib "") (part "Res2_1"))
    )
    (comp (ref "R51")
      (value "10k")
      (footprint "0603-1")
      (description "Resistor")
      (fields (field (name "PUBLISHER") "Altium Limited"))
      (libsource (lib "") (part "Res2_3"))
    )
    (comp (ref "R52")
      (value "10k")
      (footprint "0603-1")
      (description "Resistor")
      (libsource (lib "") (part "Res2_3"))
    )
    (comp (ref "R53")
      (value "150R/1W")
      (footprint "1812")
      (description "Resistor")
      (libsource (lib "") (part "Res2_3"))
    )
    (comp (ref "R54")
      (value "2k")
      (footprint "0603-1")
      (description "Resistor")
      (libsource (lib "") (part "Res2_3"))
    )
    (comp (ref "R55")
      (value "1k")
      (footprint "0603-1")
      (description "Resistor")
      (libsource (lib "") (part "Res2_2"))
    )
    (comp (ref "R56")
      (value "NC")
      (footprint "0603-1")
      (description "Resistor")
      (libsource (lib "Miscellaneous Devices") (part "Res2"))
    )
    (comp (ref "R57")
      (value "NC")
      (footprint "0603-1")
      (description "Resistor")
      (libsource (lib "Miscellaneous Devices") (part "Res2"))
    )
    (comp (ref "R58")
      (value "330R")
      (footprint "0603-1")
      (description "Resistor")
      (libsource (lib "") (part "Res2_1"))
    )
    (comp (ref "R59")
      (value "330R")
      (footprint "0603-1")
      (description "Resistor")
      (libsource (lib "") (part "Res2_1"))
    )
    (comp (ref "R60")
      (value "330R")
      (footprint "0603-1")
      (description "Resistor")
      (libsource (lib "") (part "Res2_1"))
    )
    (comp (ref "R61")
      (value "330R")
      (footprint "0603-1")
      (description "Resistor")
      (libsource (lib "") (part "Res2_1"))
    )
    (comp (ref "R62")
      (value "510R")
      (footprint "0603-1")
      (description "Resistor")
      (libsource (lib "Miscellaneous Devices") (part "Res2"))
    )
    (comp (ref "R63")
      (value "510R")
      (footprint "0603-1")
      (description "Resistor")
      (libsource (lib "Miscellaneous Devices") (part "Res2"))
    )
    (comp (ref "R64")
      (value "510R")
      (footprint "0603-1")
      (description "Resistor")
      (libsource (lib "Miscellaneous Devices") (part "Res2"))
    )
    (comp (ref "R65")
      (value "10k")
      (footprint "0603-1")
      (description "Resistor")
      (libsource (lib "") (part "Res2_1"))
    )
    (comp (ref "R66")
      (value "1k")
      (footprint "0603-1")
      (description "Resistor")
      (libsource (lib "") (part "Res2_3"))
    )
    (comp (ref "R67")
      (value "10k")
      (footprint "0603-1")
      (description "Resistor")
      (libsource (lib "Miscellaneous Devices") (part "Res2"))
    )
    (comp (ref "S1")
      (value "RESET")
      (footprint "TD-3580")
      (description "Switch")
      (fields (field (name "PUBLISHER") "Altium Limited"))
      (libsource (lib "Miscellaneous Devices") (part "SW-PB"))
    )
    (comp (ref "S2")
      (value "SW-PB")
      (footprint "TD-3580")
      (description "Switch")
      (fields (field (name "PUBLISHER") "Altium Limited"))
      (libsource (lib "Miscellaneous Devices") (part "SW-PB"))
    )
    (comp (ref "S3")
      (value "SW-PB")
      (footprint "TD-3580")
      (description "Switch")
      (fields (field (name "PUBLISHER") "Altium Limited"))
      (libsource (lib "Miscellaneous Devices") (part "SW-PB"))
    )
    (comp (ref "S4")
      (value "SW-PB")
      (footprint "TD-3580")
      (description "Switch")
      (fields (field (name "PUBLISHER") "Altium Limited"))
      (libsource (lib "Miscellaneous Devices") (part "SW-PB"))
    )
    (comp (ref "S5")
      (value "SW-PB")
      (footprint "TD-3580")
      (description "Switch")
      (fields (field (name "PUBLISHER") "Altium Limited"))
      (libsource (lib "Miscellaneous Devices") (part "SW-PB"))
    )
    (comp (ref "S6")
      (value "PEN")
      (footprint "SSD1210")
      (description "Single-Pole, Single-Throw Switch")
      (fields (field (name "PUBLISHER") "Altium Limited"))
      (libsource (lib "Miscellaneous Devices") (part "SW-SPST"))
    )
    (comp (ref "U1")
      (value "SAK-TC264D-40F200N BC")
      (footprint "QFP50P2200X2200X160-145N-1")
      (description "32-Bit Single-Chip Microcontroller BC-Step")
      (fields (field (name "MANUFACTURER") "Infineon Technologies"))
      (libsource (lib "") (part "SAK-TC264D-40F200N BC_1"))
    )
    (comp (ref "U2")
      (value "XC6206P132(1.3V)")
      (footprint "SOT-23-3")
      (description "Connector")
      (libsource (lib "MySchLib") (part "CON3"))
    )
    (comp (ref "U3")
      (value "AD8606")
      (footprint "SO-8")
      (fields (field (name "MANUFACTURER") "Analog Devices") (field (name "PARTNUMBER") "AD8606ARZ-REEL7"))
      (libsource (lib "") (part "AD8606ARZ-REEL7_1"))
    )
    (comp (ref "U4")
      (value "AD8606")
      (footprint "SO-8")
      (fields (field (name "MANUFACTURER") "Analog Devices") (field (name "PARTNUMBER") "AD8606ARZ-REEL7"))
      (libsource (lib "") (part "AD8606ARZ-REEL7_1"))
    )
    (comp (ref "U5")
      (value "AD8606")
      (footprint "SO-8")
      (fields (field (name "MANUFACTURER") "Analog Devices") (field (name "PARTNUMBER") "AD8606ARZ-REEL7"))
      (libsource (lib "Analog Devices Operational Amplifiers") (part "AD8606ARZ-REEL7"))
    )
    (comp (ref "U6")
      (value "Si8274AB1-IM1")
      (footprint "LGA-14_L5.0-W5.0-P0.65-BL")
      (libsource (lib "my_library") (part "Si8274AB1-IM1"))
    )
    (comp (ref "U7")
      (value "Si8274AB1-IM1")
      (footprint "LGA-14_L5.0-W5.0-P0.65-BL")
      (libsource (lib "my_library") (part "Si8274AB1-IM1"))
    )
    (comp (ref "U8")
      (value "Si8274AB1-IM1")
      (footprint "LGA-14_L5.0-W5.0-P0.65-BL")
      (libsource (lib "my_library") (part "Si8274AB1-IM1"))
    )
    (comp (ref "U9")
      (value "Si8274AB1-IM1")
      (footprint "LGA-14_L5.0-W5.0-P0.65-BL")
      (libsource (lib "my_library") (part "Si8274AB1-IM1"))
    )
    (comp (ref "U10")
      (value "WRB1205SD-3WR2")
      (footprint "WRB_SD-3WR2")
      (libsource (lib "my_library") (part "WRB_SD-3WR2"))
    )
    (comp (ref "U11")
      (value "TPS73633DBVR")
      (footprint "SOT-23-5")
      (fields (field (name "MANUFACTURER") "Texas Instruments"))
      (libsource (lib "TI Power Management Linear Regulator Single Channel LDO (400-7500mA)") (part "TPS73633DBVR"))
    )
    (comp (ref "U12")
      (value "TPS73633DBVR")
      (footprint "SOT-23-5")
      (fields (field (name "MANUFACTURER") "Texas Instruments"))
      (libsource (lib "TI Power Management Linear Regulator Single Channel LDO (400-7500mA)") (part "TPS73633DBVR"))
    )
    (comp (ref "U13")
      (value "PC817")
      (footprint "DIP-4")
      (description "4-Pin Phototransistor Optocoupler")
      (fields (field (name "PUBLISHER") "Altium Limited"))
      (libsource (lib "Miscellaneous Devices") (part "Optoisolator1"))
    )
    (comp (ref "Y1") (value "20MHz") (footprint "CFPX-5") (libsource (lib "my_library") (part "XTAL")))
  )
  (nets
    (net (code "1") (name "/AHO1") (class "Default")
      (node (ref "R37") (pin "1") (pinfunction "1_1") (pintype "passive"))
      (node (ref "U6") (pin "13") (pinfunction "VOA_13") (pintype "passive"))
    )
    (net (code "2") (name "/AHO2") (class "Default")
      (node (ref "R45") (pin "1") (pinfunction "1_1") (pintype "passive"))
      (node (ref "U8") (pin "13") (pinfunction "VOA_13") (pintype "passive"))
    )
    (net (code "3") (name "/AHS1") (class "Default")
      (node (ref "C36") (pin "2") (pinfunction "2_2") (pintype "passive"))
      (node (ref "Q2") (pin "5") (pinfunction "D2_5") (pintype "passive"))
      (node (ref "U6") (pin "12") (pinfunction "GNDA_12") (pintype "passive"))
    )
    (net (code "4") (name "/AHS2") (class "Default")
      (node (ref "C42") (pin "2") (pinfunction "2_2") (pintype "passive"))
      (node (ref "Q4") (pin "5") (pinfunction "D2_5") (pintype "passive"))
      (node (ref "U8") (pin "12") (pinfunction "GNDA_12") (pintype "passive"))
    )
    (net (code "5") (name "/ALO1") (class "Default")
      (node (ref "R38") (pin "1") (pinfunction "1_1") (pintype "passive"))
      (node (ref "U6") (pin "9") (pinfunction "VOB_9") (pintype "passive"))
    )
    (net (code "6") (name "/ALO2") (class "Default")
      (node (ref "R46") (pin "1") (pinfunction "1_1") (pintype "passive"))
      (node (ref "U8") (pin "9") (pinfunction "VOB_9") (pintype "passive"))
    )
    (net (code "7") (name "/AN0") (class "Default")
      (node (ref "C24") (pin "2") (pinfunction "2_2") (pintype "passive"))
      (node (ref "D3") (pin "2") (pinfunction "2_2") (pintype "passive"))
      (node (ref "R19") (pin "1") (pinfunction "1_1") (pintype "passive"))
      (node (ref "U1") (pin "57") (pinfunction "AN0_57") (pintype "input"))
    )
    (net (code "8") (name "/AN1") (class "Default")
      (node (ref "C22") (pin "2") (pinfunction "2_2") (pintype "passive"))
      (node (ref "D2") (pin "2") (pinfunction "2_2") (pintype "passive"))
      (node (ref "R15") (pin "1") (pinfunction "1_1") (pintype "passive"))
      (node (ref "U1") (pin "56") (pinfunction "AN1_56") (pintype "input"))
    )
    (net (code "9") (name "/AN2") (class "Default")
      (node (ref "C29") (pin "2") (pinfunction "2_2") (pintype "passive"))
      (node (ref "D5") (pin "2") (pinfunction "2_2") (pintype "passive"))
      (node (ref "R27") (pin "1") (pinfunction "1_1") (pintype "passive"))
      (node (ref "U1") (pin "55") (pinfunction "AN2_55") (pintype "input"))
    )
    (net (code "10") (name "/AN3") (class "Default")
      (node (ref "C27") (pin "2") (pinfunction "2_2") (pintype "passive"))
      (node (ref "D4") (pin "2") (pinfunction "2_2") (pintype "passive"))
      (node (ref "R23") (pin "1") (pinfunction "1_1") (pintype "passive"))
      (node (ref "U1") (pin "54") (pinfunction "AN3_54") (pintype "input"))
    )
    (net (code "11") (name "/AN4") (class "Default")
      (node (ref "C32") (pin "2") (pinfunction "2_2") (pintype "passive"))
      (node (ref "D6") (pin "2") (pinfunction "2_2") (pintype "passive"))
      (node (ref "R31") (pin "1") (pinfunction "1_1") (pintype "passive"))
      (node (ref "U1") (pin "53") (pinfunction "AN4_53") (pintype "input"))
    )
    (net (code "37") (name "/BHO1") (class "Default")
      (node (ref "R41") (pin "1") (pinfunction "1_1") (pintype "passive"))
      (node (ref "U7") (pin "13") (pinfunction "VOA_13") (pintype "passive"))
    )
    (net (code "38") (name "/BHO2") (class "Default")
      (node (ref "R49") (pin "1") (pinfunction "1_1") (pintype "passive"))
      (node (ref "U9") (pin "13") (pinfunction "VOA_13") (pintype "passive"))
    )
    (net (code "39") (name "/BHS1") (class "Default")
      (node (ref "C39") (pin "2") (pinfunction "2_2") (pintype "passive"))
      (node (ref "Q3") (pin "5") (pinfunction "D2_5") (pintype "passive"))
      (node (ref "U7") (pin "12") (pinfunction "GNDA_12") (pintype "passive"))
    )
    (net (code "40") (name "/BHS2") (class "Default")
      (node (ref "C45") (pin "2") (pinfunction "2_2") (pintype "passive"))
      (node (ref "Q5") (pin "5") (pinfunction "D2_5") (pintype "passive"))
      (node (ref "U9") (pin "12") (pinfunction "GNDA_12") (pintype "passive"))
    )
    (net (code "41") (name "/BLO1") (class "Default")
      (node (ref "R42") (pin "1") (pinfunction "1_1") (pintype "passive"))
      (node (ref "U7") (pin "9") (pinfunction "VOB_9") (pintype "passive"))
    )
    (net (code "42") (name "/BLO2") (class "Default")
      (node (ref "R50") (pin "1") (pinfunction "1_1") (pintype "passive"))
      (node (ref "U9") (pin "9") (pinfunction "VOB_9") (pintype "passive"))
    )
    (net (code "43") (name "/EN") (class "Default")
      (node (ref "JP1") (pin "1") (pinfunction "C1_1") (pintype "passive"))
      (node (ref "R51") (pin "1") (pinfunction "1_1") (pintype "passive"))
      (node (ref "U6") (pin "5") (pinfunction "EN_5") (pintype "passive"))
      (node (ref "U7") (pin "5") (pinfunction "EN_5") (pintype "passive"))
      (node (ref "U8") (pin "5") (pinfunction "EN_5") (pintype "passive"))
      (node (ref "U9") (pin "5") (pinfunction "EN_5") (pintype "passive"))
    )
    (net (code "44") (name "/ESR0") (class "Default")
      (node (ref "R11") (pin "2") (pinfunction "2_2") (pintype "passive"))
      (node (ref "U1") (pin "98") (pinfunction "ESR0_N_98") (pintype "bidirectional"))
    )
    (net (code "45") (name "/ESR1") (class "Default")
      (node (ref "U1") (pin "96") (pinfunction "ESR1_N_96") (pintype "bidirectional+no_connect"))
    )
    (net (code "46") (name "/FGND") (class "Default")
      (node (ref "C34") (pin "2") (pinfunction "2_2") (pintype "passive"))
      (node (ref "P2") (pin "1") (pinfunction "1_1") (pintype "passive"))
      (node (ref "P2") (pin "3") (pinfunction "3_3") (pintype "passive"))
      (node (ref "P2") (pin "5") (pinfunction "5_5") (pintype "passive"))
      (node (ref "P2") (pin "7") (pinfunction "7_7") (pintype "passive"))
      (node (ref "P2") (pin "9") (pinfunction "9_9") (pintype "passive"))
      (node (ref "R13") (pin "1") (pinfunction "1_1") (pintype "passive"))
      (node (ref "R17") (pin "1") (pinfunction "1_1") (pintype "passive"))
      (node (ref "R21") (pin "1") (pinfunction "1_1") (pintype "passive"))
      (node (ref "R25") (pin "1") (pinfunction "1_1") (pintype "passive"))
      (node (ref "R29") (pin "1") (pinfunction "1_1") (pintype "passive"))
      (node (ref "U5") (pin "1") (pinfunction "OUT_A_1") (pintype "output"))
      (node (ref "U5") (pin "2") (pinfunction "-IN_A_2") (pintype "input"))
    )
    (net (code "47") (name "/IN1") (class "Default")
      (node (ref "P2") (pin "10") (pinfunction "10_10") (pintype "passive"))
      (node (ref "R20") (pin "1") (pinfunction "1_1") (pintype "passive"))
    )
    (net (code "48") (name "/IN2") (class "Default")
      (node (ref "P2") (pin "8") (pinfunction "8_8") (pintype "passive"))
      (node (ref "R16") (pin "1") (pinfunction "1_1") (pintype "passive"))
    )
    (net (code "49") (name "/IN3") (class "Default")
      (node (ref "P2") (pin "6") (pinfunction "6_6") (pintype "passive"))
      (node (ref "R28") (pin "1") (pinfunction "1_1") (pintype "passive"))
    )
    (net (code "50") (name "/IN4") (class "Default")
      (node (ref "P2") (pin "4") (pinfunction "4_4") (pintype "passive"))
      (node (ref "R24") (pin "1") (pinfunction "1_1") (pintype "passive"))
    )
    (net (code "51") (name "/IN5") (class "Default")
      (node (ref "P2") (pin "2") (pinfunction "2_2") (pintype "passive"))
      (node (ref "R32") (pin "1") (pinfunction "1_1") (pintype "passive"))
    )
    (net (code "52") (name "/P00.0") (class "Default")
      (node (ref "P4") (pin "8") (pinfunction "8_8") (pintype "passive"))
      (node (ref "U1") (pin "11") (pinfunction "P00_0_11") (pintype "bidirectional"))
    )
    (net (code "53") (name "/P00.1") (class "Default")
      (node (ref "P4") (pin "9") (pinfunction "9_9") (pintype "passive"))
      (node (ref "U1") (pin "12") (pinfunction "P00_1_12") (pintype "bidirectional"))
    )
    (net (code "54") (name "/P00.2") (class "Default")
      (node (ref "P4") (pin "10") (pinfunction "10_10") (pintype "passive"))
      (node (ref "U1") (pin "13") (pinfunction "P00_2_13") (pintype "bidirectional"))
    )
    (net (code "55") (name "/P00.3") (class "Default")
      (node (ref "P4") (pin "11") (pinfunction "11_11") (pintype "passive"))
      (node (ref "U1") (pin "14") (pinfunction "P00_3_14") (pintype "bidirectional"))
    )
    (net (code "56") (name "/P00.4") (class "Default")
      (node (ref "P4") (pin "12") (pinfunction "12_12") (pintype "passive"))
      (node (ref "U1") (pin "15") (pinfunction "P00_4_15") (pintype "bidirectional"))
    )
    (net (code "57") (name "/P00.5") (class "Default")
      (node (ref "P4") (pin "13") (pinfunction "13_13") (pintype "passive"))
      (node (ref "U1") (pin "16") (pinfunction "P00_5_16") (pintype "bidirectional"))
    )
    (net (code "58") (name "/P00.6") (class "Default")
      (node (ref "P4") (pin "14") (pinfunction "14_14") (pintype "passive"))
      (node (ref "U1") (pin "17") (pinfunction "P00_6_17") (pintype "bidirectional"))
    )
    (net (code "59") (name "/P00.7") (class "Default")
      (node (ref "P4") (pin "15") (pinfunction "15_15") (pintype "passive"))
      (node (ref "U1") (pin "18") (pinfunction "P00_7_18") (pintype "bidirectional"))
    )
    (net (code "63") (name "/P02.0") (class "Default")
      (node (ref "P4") (pin "1") (pinfunction "1_1") (pintype "passive"))
      (node (ref "R57") (pin "2") (pinfunction "2_2") (pintype "passive"))
      (node (ref "U1") (pin "1") (pinfunction "P02_0_1") (pintype "bidirectional"))
    )
    (net (code "64") (name "/P02.1") (class "Default")
      (node (ref "P4") (pin "6") (pinfunction "6_6") (pintype "passive"))
      (node (ref "R56") (pin "2") (pinfunction "2_2") (pintype "passive"))
      (node (ref "U1") (pin "2") (pinfunction "P02_1_2") (pintype "bidirectional"))
    )
    (net (code "65") (name "/P02.2") (class "Default")
      (node (ref "P4") (pin "4") (pinfunction "4_4") (pintype "passive"))
      (node (ref "U1") (pin "3") (pinfunction "P02_2_3") (pintype "bidirectional"))
    )
    (net (code "66") (name "/P02.3") (class "Default")
      (node (ref "P4") (pin "3") (pinfunction "3_3") (pintype "passive"))
      (node (ref "U1") (pin "4") (pinfunction "P02_3_4") (pintype "bidirectional"))
    )
    (net (code "67") (name "/P02.4") (class "Default")
      (node (ref "P10") (pin "2") (pinfunction "2_2") (pintype "passive"))
      (node (ref "U1") (pin "5") (pinfunction "P02_4_5") (pintype "bidirectional"))
    )
    (net (code "68") (name "/P02.5") (class "Default")
      (node (ref "U1") (pin "6") (pinfunction "P02_5_6") (pintype "bidirectional"))
      (node (ref "U13") (pin "2") (pinfunction "K_2") (pintype "passive"))
    )
    (net (code "75") (name "/P10.5") (class "Default")
      (node (ref "R7") (pin "2") (pinfunction "2_2") (pintype "passive"))
      (node (ref "U1") (pin "143") (pinfunction "P10_5_143") (pintype "bidirectional"))
    )
    (net (code "76") (name "/P10.6") (class "Default")
      (node (ref "R8") (pin "2") (pinfunction "2_2") (pintype "passive"))
      (node (ref "U1") (pin "144") (pinfunction "P10_6_144") (pintype "bidirectional"))
    )
    (net (code "77") (name "/P11.2") (class "Default")
      (node (ref "P8") (pin "7") (pinfunction "7_7") (pintype "passive"))
      (node (ref "U1") (pin "132") (pinfunction "P11_2_132") (pintype "bidirectional"))
    )
    (net (code "78") (name "/P11.3") (class "Default")
      (node (ref "P8") (pin "6") (pinfunction "6_6") (pintype "passive"))
      (node (ref "U1") (pin "133") (pinfunction "P11_3_133") (pintype "bidirectional"))
    )
    (net (code "79") (name "/P11.6") (class "Default")
      (node (ref "P8") (pin "5") (pinfunction "5_5") (pintype "passive"))
      (node (ref "U1") (pin "134") (pinfunction "P11_6_134") (pintype "bidirectional"))
    )
    (net (code "80") (name "/P11.9") (class "Default")
      (node (ref "P8") (pin "4") (pinfunction "4_4") (pintype "passive"))
      (node (ref "U1") (pin "135") (pinfunction "P11_9_135") (pintype "bidirectional"))
    )
    (net (code "81") (name "/P11.10") (class "Default")
      (node (ref "P8") (pin "3") (pinfunction "3_3") (pintype "passive"))
      (node (ref "U1") (pin "137") (pinfunction "P11_10_137") (pintype "bidirectional"))
    )
    (net (code "84") (name "/P13.0") (class "Default")
      (node (ref "R58") (pin "2") (pinfunction "2_2") (pintype "passive"))
      (node (ref "U1") (pin "128") (pinfunction "P13_0_128") (pintype "bidirectional"))
    )
    (net (code "85") (name "/P13.1") (class "Default")
      (node (ref "R59") (pin "2") (pinfunction "2_2") (pintype "passive"))
      (node (ref "U1") (pin "129") (pinfunction "P13_1_129") (pintype "bidirectional"))
    )
    (net (code "86") (name "/P13.2") (class "Default")
      (node (ref "R60") (pin "2") (pinfunction "2_2") (pintype "passive"))
      (node (ref "U1") (pin "130") (pinfunction "P13_2_130") (pintype "bidirectional"))
    )
    (net (code "87") (name "/P13.3") (class "Default")
      (node (ref "R61") (pin "2") (pinfunction "2_2") (pintype "passive"))
      (node (ref "U1") (pin "131") (pinfunction "P13_3_131") (pintype "bidirectional"))
    )
    (net (code "90") (name "/P14.2") (class "Default")
      (node (ref "R4") (pin "2") (pinfunction "2_2") (pintype "passive"))
      (node (ref "U1") (pin "120") (pinfunction "P14_2_120") (pintype "bidirectional"))
    )
    (net (code "91") (name "/P14.3") (class "Default")
      (node (ref "R5") (pin "2") (pinfunction "2_2") (pintype "passive"))
      (node (ref "U1") (pin "121") (pinfunction "P14_3_121") (pintype "bidirectional"))
    )
    (net (code "92") (name "/P14.4") (class "Default")
      (node (ref "R9") (pin "2") (pinfunction "2_2") (pintype "passive"))
      (node (ref "U1") (pin "122") (pinfunction "P14_4_122") (pintype "bidirectional"))
    )
    (net (code "93") (name "/P14.5") (class "Default")
      (node (ref "R3") (pin "2") (pinfunction "2_2") (pintype "passive"))
      (node (ref "U1") (pin "123") (pinfunction "P14_5_123") (pintype "bidirectional"))
    )
    (net (code "94") (name "/P14.6") (class "Default")
      (node (ref "R2") (pin "2") (pinfunction "2_2") (pintype "passive"))
      (node (ref "U1") (pin "124") (pinfunction "P14_6_124") (pintype "bidirectional"))
    )
    (net (code "95") (name "/P15.0") (class "Default")
      (node (ref "R63") (pin "1") (pinfunction "1_1") (pintype "passive"))
      (node (ref "U1") (pin "109") (pinfunction "P15_0_109") (pintype "bidirectional"))
    )
    (net (code "96") (name "/P15.1") (class "Default")
      (node (ref "R62") (pin "1") (pinfunction "1_1") (pintype "passive"))
      (node (ref "U1") (pin "110") (pinfunction "P15_1_110") (pintype "bidirectional"))
    )
    (net (code "97") (name "/P15.2") (class "Default")
      (node (ref "R64") (pin "1") (pinfunction "1_1") (pintype "passive"))
      (node (ref "U1") (pin "111") (pinfunction "P15_2_111") (pintype "bidirectional"))
    )
    (net (code "101") (name "/P15.6") (class "Default")
      (node (ref "P11") (pin "3") (pinfunction "3_3") (pintype "passive"))
      (node (ref "U1") (pin "115") (pinfunction "P15_6_115") (pintype "bidirectional"))
    )
    (net (code "102") (name "/P15.7") (class "Default")
      (node (ref "P11") (pin "4") (pinfunction "4_4") (pintype "passive"))
      (node (ref "U1") (pin "116") (pinfunction "P15_7_116") (pintype "bidirectional"))
    )
    (net (code "104") (name "/P20.0") (class "Default")
      (node (ref "P6") (pin "3") (pinfunction "3_3") (pintype "passive"))
      (node (ref "U1") (pin "93") (pinfunction "P20_0_93") (pintype "bidirectional"))
    )
    (net (code "105") (name "/P20.2") (class "Default")
      (node (ref "R10") (pin "2") (pinfunction "2_2") (pintype "passive"))
      (node (ref "U1") (pin "94") (pinfunction "P20_2/TESTMODE_N_94") (pintype "bidirectional"))
    )
    (net (code "106") (name "/P20.3") (class "Default")
      (node (ref "P6") (pin "4") (pinfunction "4_4") (pintype "passive"))
      (node (ref "U1") (pin "95") (pinfunction "P20_3_95") (pintype "bidirectional"))
    )
    (net (code "116") (name "/P21.2") (class "Default")
      (node (ref "R39") (pin "2") (pinfunction "2_2") (pintype "passive"))
      (node (ref "U1") (pin "84") (pinfunction "P21_2_84") (pintype "bidirectional"))
      (node (ref "U7") (pin "2") (pinfunction "PWM_2") (pintype "passive"))
    )
    (net (code "117") (name "/P21.3") (class "Default")
      (node (ref "R35") (pin "2") (pinfunction "2_2") (pintype "passive"))
      (node (ref "U1") (pin "85") (pinfunction "P21_3_85") (pintype "bidirectional"))
      (node (ref "U6") (pin "2") (pinfunction "PWM_2") (pintype "passive"))
    )
    (net (code "118") (name "/P21.4") (class "Default")
      (node (ref "R47") (pin "2") (pinfunction "2_2") (pintype "passive"))
      (node (ref "U1") (pin "86") (pinfunction "P21_4_86") (pintype "bidirectional"))
      (node (ref "U9") (pin "2") (pinfunction "PWM_2") (pintype "passive"))
    )
    (net (code "119") (name "/P21.5") (class "Default")
      (node (ref "R43") (pin "2") (pinfunction "2_2") (pintype "passive"))
      (node (ref "U1") (pin "87") (pinfunction "P21_5_87") (pintype "bidirectional"))
      (node (ref "U8") (pin "2") (pinfunction "PWM_2") (pintype "passive"))
    )
    (net (code "121") (name "/P21.7") (class "Default")
      (node (ref "P1") (pin "6") (pinfunction "6_6") (pintype "passive"))
      (node (ref "U1") (pin "90") (pinfunction "P21_7/TDO_90") (pintype "bidirectional"))
    )
    (net (code "130") (name "/P33.6") (class "Default")
      (node (ref "P5") (pin "3") (pinfunction "3_3") (pintype "passive"))
      (node (ref "U1") (pin "62") (pinfunction "P33_6_62") (pintype "bidirectional"))
    )
    (net (code "131") (name "/P33.7") (class "Default")
      (node (ref "P5") (pin "4") (pinfunction "4_4") (pintype "passive"))
      (node (ref "U1") (pin "63") (pinfunction "P33_7_63") (pintype "bidirectional"))
    )
    (net (code "132") (name "/P33.8") (class "Default")
      (node (ref "P7") (pin "3") (pinfunction "3_3") (pintype "passive"))
      (node (ref "U1") (pin "64") (pinfunction "P33_8_64") (pintype "bidirectional"))
    )
    (net (code "133") (name "/P33.9") (class "Default")
      (node (ref "P7") (pin "4") (pinfunction "4_4") (pintype "passive"))
      (node (ref "U1") (pin "65") (pinfunction "P33_9_65") (pintype "bidirectional"))
    )
    (net (code "136") (name "/P33.12") (class "Default")
      (node (ref "P9") (pin "1") (pinfunction "1_1") (pintype "passive"))
      (node (ref "U1") (pin "68") (pinfunction "P33_12_68") (pintype "bidirectional"))
    )
    (net (code "137") (name "/P33.13") (class "Default")
      (node (ref "P9") (pin "2") (pinfunction "2_2") (pintype "passive"))
      (node (ref "U1") (pin "69") (pinfunction "P33_13_69") (pintype "bidirectional"))
    )
    (net (code "138") (name "/PEN") (class "Default")
      (node (ref "C78") (pin "1") (pinfunction "1_1") (pintype "passive"))
      (node (ref "R65") (pin "2") (pinfunction "2_2") (pintype "passive"))
      (node (ref "S6") (pin "1") (pinfunction "COMMON_1") (pintype "passive"))
      (node (ref "U11") (pin "3") (pinfunction "EN_3") (pintype "input"))
      (node (ref "U12") (pin "3") (pinfunction "EN_3") (pintype "input"))
    )
    (net (code "139") (name "/RST") (class "Default")
      (node (ref "C3") (pin "2") (pinfunction "2_2") (pintype "passive"))
      (node (ref "P1") (pin "10") (pinfunction "10_10") (pintype "passive"))
      (node (ref "R1") (pin "2") (pinfunction "2_2") (pintype "passive"))
      (node (ref "S1") (pin "2") (pinfunction "2_2") (pintype "passive"))
      (node (ref "U1") (pin "97") (pinfunction "PORST_N_97") (pintype "input"))
    )
    (net (code "140") (name "/TCK") (class "Default")
      (node (ref "P1") (pin "4") (pinfunction "4_4") (pintype "passive"))
      (node (ref "U1") (pin "92") (pinfunction "TCK_92") (pintype "input"))
    )
    (net (code "141") (name "/TMS") (class "Default")
      (node (ref "P1") (pin "2") (pinfunction "2_2") (pintype "passive"))
      (node (ref "U1") (pin "89") (pinfunction "TMS_89") (pintype "input"))
    )
    (net (code "142") (name "/TRST") (class "Default")
      (node (ref "P1") (pin "8") (pinfunction "8_8") (pintype "passive"))
      (node (ref "R6") (pin "2") (pinfunction "2_2") (pintype "passive"))
      (node (ref "U1") (pin "91") (pinfunction "TRST_N_91") (pintype "input"))
    )
    (net (code "143") (name "/XTAL1") (class "Default")
      (node (ref "C1") (pin "2") (pinfunction "2_2") (pintype "passive"))
      (node (ref "U1") (pin "81") (pinfunction "XTAL1_81") (pintype "input"))
      (node (ref "Y1") (pin "3") (pinfunction "3_3") (pintype "passive"))
    )
    (net (code "144") (name "/XTAL2") (class "Default")
      (node (ref "C2") (pin "2") (pinfunction "2_2") (pintype "passive"))
      (node (ref "U1") (pin "82") (pinfunction "XTAL2_82") (pintype "output"))
      (node (ref "Y1") (pin "1") (pinfunction "1_1") (pintype "passive"))
    )
    (net (code "145") (name "AVCC_3V3_ISOL") (class "Default")
      (node (ref "C25") (pin "1") (pinfunction "1_1") (pintype "passive"))
      (node (ref "C30") (pin "1") (pinfunction "1_1") (pintype "passive"))
      (node (ref "C35") (pin "1") (pinfunction "1_1") (pintype "passive"))
      (node (ref "C4") (pin "1") (pinfunction "1_1") (pintype "passive"))
      (node (ref "C54") (pin "1") (pinfunction "1_1") (pintype "passive"))
      (node (ref "L1") (pin "2") (pinfunction "2_2") (pintype "passive"))
      (node (ref "R33") (pin "1") (pinfunction "1_1") (pintype "passive"))
      (node (ref "U1") (pin "42") (pinfunction "VAREF1_42") (pintype "power_in"))
      (node (ref "U3") (pin "8") (pinfunction "+V_8") (pintype "power_in"))
      (node (ref "U4") (pin "8") (pinfunction "+V_8") (pintype "power_in"))
      (node (ref "U5") (pin "8") (pinfunction "+V_8") (pintype "power_in"))
    )
    (net (code "146") (name "DVCC_3V3_ISOL") (class "Default")
      (node (ref "C10") (pin "1") (pinfunction "1_1") (pintype "passive"))
      (node (ref "C12") (pin "1") (pinfunction "1_1") (pintype "passive"))
      (node (ref "C13") (pin "1") (pinfunction "1_1") (pintype "passive"))
      (node (ref "C14") (pin "1") (pinfunction "1_1") (pintype "passive"))
      (node (ref "C15") (pin "1") (pinfunction "1_1") (pintype "passive"))
      (node (ref "C16") (pin "1") (pinfunction "1_1") (pintype "passive"))
      (node (ref "C19") (pin "2") (pinfunction "2_2") (pintype "passive"))
      (node (ref "C38") (pin "2") (pinfunction "2_2") (pintype "passive"))
      (node (ref "C41") (pin "2") (pinfunction "2_2") (pintype "passive"))
      (node (ref "C44") (pin "2") (pinfunction "2_2") (pintype "passive"))
      (node (ref "C47") (pin "2") (pinfunction "2_2") (pintype "passive"))
      (node (ref "C53") (pin "1") (pinfunction "1_1") (pintype "passive"))
      (node (ref "C86") (pin "2") (pinfunction "2_2") (pintype "passive"))
      (node (ref "C87") (pin "2") (pinfunction "2_2") (pintype "passive"))
      (node (ref "C88") (pin "2") (pinfunction "2_2") (pintype "passive"))
      (node (ref "C89") (pin "2") (pinfunction "2_2") (pintype "passive"))
      (node (ref "C9") (pin "1") (pinfunction "1_1") (pintype "passive"))
      (node (ref "D16") (pin "2") (pinfunction "2_2") (pintype "passive"))
      (node (ref "D17") (pin "1") (pinfunction "A_1") (pintype "passive"))
      (node (ref "L1") (pin "1") (pinfunction "1_1") (pintype "passive"))
      (node (ref "Q1") (pin "2") (pinfunction "S_2") (pintype "passive"))
      (node (ref "R1") (pin "1") (pinfunction "1_1") (pintype "passive"))
      (node (ref "R10") (pin "1") (pinfunction "1_1") (pintype "passive"))
      (node (ref "R51") (pin "2") (pinfunction "2_2") (pintype "passive"))
      (node (ref "R55") (pin "1") (pinfunction "1_1") (pintype "passive"))
      (node (ref "R6") (pin "1") (pinfunction "1_1") (pintype "passive"))
      (node (ref "R7") (pin "1") (pinfunction "1_1") (pintype "passive"))
      (node (ref "R8") (pin "1") (pinfunction "1_1") (pintype "passive"))
      (node (ref "R9") (pin "1") (pinfunction "1_1") (pintype "passive"))
      (node (ref "U1") (pin "125") (pinfunction "VEXT_125") (pintype "power_in"))
      (node (ref "U1") (pin "126") (pinfunction "VDDP3_126") (pintype "power_in"))
      (node (ref "U1") (pin "127") (pinfunction "VDDFL3_127") (pintype "power_in"))
      (node (ref "U1") (pin "136") (pinfunction "VFLEX_136") (pintype "power_in"))
      (node (ref "U1") (pin "23") (pinfunction "VEXT_23") (pintype "power_in"))
      (node (ref "U1") (pin "44") (pinfunction "VDDM_44") (pintype "power_in"))
      (node (ref "U1") (pin "59") (pinfunction "VEXT_59") (pintype "power_in"))
      (node (ref "U1") (pin "78") (pinfunction "VEXT_78") (pintype "power_in"))
      (node (ref "U1") (pin "83") (pinfunction "VDDP3_83") (pintype "power_in"))
      (node (ref "U11") (pin "5") (pinfunction "OUT_5") (pintype "power_in"))
      (node (ref "U2") (pin "3") (pinfunction "3_3") (pintype "passive"))
      (node (ref "U6") (pin "7") (pinfunction "VDDI_7") (pintype "passive"))
      (node (ref "U7") (pin "7") (pinfunction "VDDI_7") (pintype "passive"))
      (node (ref "U8") (pin "7") (pinfunction "VDDI_7") (pintype "passive"))
      (node (ref "U9") (pin "7") (pinfunction "VDDI_7") (pintype "passive"))
    )
    (net (code "147") (name "IGND") (class "Default")
      (node (ref "C1") (pin "1") (pinfunction "1_1") (pintype "passive"))
      (node (ref "C10") (pin "2") (pinfunction "2_2") (pintype "passive"))
      (node (ref "C11") (pin "2") (pinfunction "2_2") (pintype "passive"))
      (node (ref "C12") (pin "2") (pinfunction "2_2") (pintype "passive"))
      (node (ref "C13") (pin "2") (pinfunction "2_2") (pintype "passive"))
      (node (ref "C14") (pin "2") (pinfunction "2_2") (pintype "passive"))
      (node (ref "C15") (pin "2") (pinfunction "2_2") (pintype "passive"))
      (node (ref "C16") (pin "2") (pinfunction "2_2") (pintype "passive"))
      (node (ref "C19") (pin "1") (pinfunction "1_1") (pintype "passive"))
      (node (ref "C2") (pin "1") (pinfunction "1_1") (pintype "passive"))
      (node (ref "C22") (pin "1") (pinfunction "1_1") (pintype "passive"))
      (node (ref "C24") (pin "1") (pinfunction "1_1") (pintype "passive"))
      (node (ref "C25") (pin "2") (pinfunction "2_2") (pintype "passive"))
      (node (ref "C27") (pin "1") (pinfunction "1_1") (pintype "passive"))
      (node (ref "C29") (pin "1") (pinfunction "1_1") (pintype "passive"))
      (node (ref "C3") (pin "1") (pinfunction "1_1") (pintype "passive"))
      (node (ref "C30") (pin "2") (pinfunction "2_2") (pintype "passive"))
      (node (ref "C32") (pin "1") (pinfunction "1_1") (pintype "passive"))
      (node (ref "C33") (pin "2") (pinfunction "2_2") (pintype "passive"))
      (node (ref "C34") (pin "1") (pinfunction "1_1") (pintype "passive"))
      (node (ref "C35") (pin "2") (pinfunction "2_2") (pintype "passive"))
      (node (ref "C38") (pin "1") (pinfunction "1_1") (pintype "passive"))
      (node (ref "C4") (pin "2") (pinfunction "2_2") (pintype "passive"))
      (node (ref "C41") (pin "1") (pinfunction "1_1") (pintype "passive"))
      (node (ref "C44") (pin "1") (pinfunction "1_1") (pintype "passive"))
      (node (ref "C47") (pin "1") (pinfunction "1_1") (pintype "passive"))
      (node (ref "C5") (pin "2") (pinfunction "2_2") (pintype "passive"))
      (node (ref "C50") (pin "2") (pinfunction "2_2") (pintype "passive"))
      (node (ref "C52") (pin "1") (pinfunction "1_1") (pintype "passive"))
      (node (ref "C53") (pin "2") (pinfunction "2_2") (pintype "passive"))
      (node (ref "C54") (pin "2") (pinfunction "2_2") (pintype "passive"))
      (node (ref "C55") (pin "2") (pinfunction "2_2") (pintype "passive"))
      (node (ref "C56") (pin "1") (pinfunction "1_1") (pintype "passive"))
      (node (ref "C57") (pin "2") (pinfunction "2_2") (pintype "passive"))
      (node (ref "C58") (pin "2") (pinfunction "2_2") (pintype "passive"))
      (node (ref "C59") (pin "1") (pinfunction "1_1") (pintype "passive"))
      (node (ref "C6") (pin "2") (pinfunction "2_2") (pintype "passive"))
      (node (ref "C60") (pin "2") (pinfunction "2_2") (pintype "passive"))
      (node (ref "C62") (pin "2") (pinfunction "2_2") (pintype "passive"))
      (node (ref "C63") (pin "2") (pinfunction "2_2") (pintype "passive"))
      (node (ref "C64") (pin "2") (pinfunction "2_2") (pintype "passive"))
      (node (ref "C65") (pin "2") (pinfunction "2_2") (pintype "passive"))
      (node (ref "C66") (pin "2") (pinfunction "2_2") (pintype "passive"))
      (node (ref "C67") (pin "2") (pinfunction "2_2") (pintype "passive"))
      (node (ref "C7") (pin "2") (pinfunction "2_2") (pintype "passive"))
      (node (ref "C78") (pin "2") (pinfunction "2_2") (pintype "passive"))
      (node (ref "C8") (pin "2") (pinfunction "2_2") (pintype "passive"))
      (node (ref "C86") (pin "1") (pinfunction "1_1") (pintype "passive"))
      (node (ref "C87") (pin "1") (pinfunction "1_1") (pintype "passive"))
      (node (ref "C88") (pin "1") (pinfunction "1_1") (pintype "passive"))
      (node (ref "C89") (pin "1") (pinfunction "1_1") (pintype "passive"))
      (node (ref "C9") (pin "2") (pinfunction "2_2") (pintype "passive"))
      (node (ref "C90") (pin "2") (pinfunction "2_2") (pintype "passive"))
      (node (ref "C91") (pin "2") (pinfunction "2_2") (pintype "passive"))
      (node (ref "D2") (pin "1") (pinfunction "1_1") (pintype "passive"))
      (node (ref "D3") (pin "1") (pinfunction "1_1") (pintype "passive"))
      (node (ref "D4") (pin "1") (pinfunction "1_1") (pintype "passive"))
      (node (ref "D5") (pin "1") (pinfunction "1_1") (pintype "passive"))
      (node (ref "D6") (pin "1") (pinfunction "1_1") (pintype "passive"))
      (node (ref "JP1") (pin "2") (pinfunction "C2_2") (pintype "passive"))
      (node (ref "P1") (pin "3") (pinfunction "3_3") (pintype "passive"))
      (node (ref "P1") (pin "5") (pinfunction "5_5") (pintype "passive"))
      (node (ref "P1") (pin "7") (pinfunction "7_7") (pintype "passive"))
      (node (ref "P1") (pin "9") (pinfunction "9_9") (pintype "passive"))
      (node (ref "P10") (pin "1") (pinfunction "1_1") (pintype "passive"))
      (node (ref "P11") (pin "2") (pinfunction "2_2") (pintype "passive"))
      (node (ref "P4") (pin "16") (pinfunction "16_16") (pintype "passive"))
      (node (ref "P4") (pin "2") (pinfunction "2_2") (pintype "passive"))
      (node (ref "P4") (pin "7") (pinfunction "7_7") (pintype "passive"))
      (node (ref "P5") (pin "6") (pinfunction "6_6") (pintype "passive"))
      (node (ref "P6") (pin "6") (pinfunction "6_6") (pintype "passive"))
      (node (ref "P7") (pin "2") (pinfunction "2_2") (pintype "passive"))
      (node (ref "P8") (pin "1") (pinfunction "1_1") (pintype "passive"))
      (node (ref "P9") (pin "4") (pinfunction "4_4") (pintype "passive"))
      (node (ref "R12") (pin "1") (pinfunction "1_1") (pintype "passive"))
      (node (ref "R15") (pin "2") (pinfunction "2_2") (pintype "passive"))
      (node (ref "R19") (pin "2") (pinfunction "2_2") (pintype "passive"))
      (node (ref "R2") (pin "1") (pinfunction "1_1") (pintype "passive"))
      (node (ref "R23") (pin "2") (pinfunction "2_2") (pintype "passive"))
      (node (ref "R27") (pin "2") (pinfunction "2_2") (pintype "passive"))
      (node (ref "R3") (pin "1") (pinfunction "1_1") (pintype "passive"))
      (node (ref "R31") (pin "2") (pinfunction "2_2") (pintype "passive"))
      (node (ref "R34") (pin "2") (pinfunction "2_2") (pintype "passive"))
      (node (ref "R35") (pin "1") (pinfunction "1_1") (pintype "passive"))
      (node (ref "R36") (pin "1") (pinfunction "1_1") (pintype "passive"))
      (node (ref "R39") (pin "1") (pinfunction "1_1") (pintype "passive"))
      (node (ref "R4") (pin "1") (pinfunction "1_1") (pintype "passive"))
      (node (ref "R40") (pin "1") (pinfunction "1_1") (pintype "passive"))
      (node (ref "R43") (pin "1") (pinfunction "1_1") (pintype "passive"))
      (node (ref "R44") (pin "1") (pinfunction "1_1") (pintype "passive"))
      (node (ref "R47") (pin "1") (pinfunction "1_1") (pintype "passive"))
      (node (ref "R48") (pin "1") (pinfunction "1_1") (pintype "passive"))
      (node (ref "R5") (pin "1") (pinfunction "1_1") (pintype "passive"))
      (node (ref "R53") (pin "1") (pinfunction "1_1") (pintype "passive"))
      (node (ref "R54") (pin "1") (pinfunction "1_1") (pintype "passive"))
      (node (ref "R56") (pin "1") (pinfunction "1_1") (pintype "passive"))
      (node (ref "R57") (pin "1") (pinfunction "1_1") (pintype "passive"))
      (node (ref "R66") (pin "1") (pinfunction "1_1") (pintype "passive"))
      (node (ref "S1") (pin "1") (pinfunction "1_1") (pintype "passive"))
      (node (ref "S2") (pin "1") (pinfunction "1_1") (pintype "passive"))
      (node (ref "S3") (pin "1") (pinfunction "1_1") (pintype "passive"))
      (node (ref "S4") (pin "1") (pinfunction "1_1") (pintype "passive"))
      (node (ref "S5") (pin "1") (pinfunction "1_1") (pintype "passive"))
      (node (ref "S6") (pin "2") (pinfunction "NO_2") (pintype "passive"))
      (node (ref "U1") (pin "145") (pinfunction "EP_145") (pintype "power_in"))
      (node (ref "U1") (pin "41") (pinfunction "VAGND1_41") (pintype "power_in"))
      (node (ref "U1") (pin "43") (pinfunction "VSSM_43") (pintype "power_in"))
      (node (ref "U1") (pin "80") (pinfunction "VSS_80") (pintype "power_in"))
      (node (ref "U10") (pin "7") (pinfunction "0V_7") (pintype "passive"))
      (node (ref "U11") (pin "2") (pinfunction "GND_2") (pintype "power_in"))
      (node (ref "U12") (pin "2") (pinfunction "GND_2") (pintype "power_in"))
      (node (ref "U2") (pin "1") (pinfunction "1_1") (pintype "passive"))
      (node (ref "U3") (pin "4") (pinfunction "-V_4") (pintype "power_in"))
      (node (ref "U4") (pin "4") (pinfunction "-V_4") (pintype "power_in"))
      (node (ref "U5") (pin "4") (pinfunction "-V_4") (pintype "power_in"))
      (node (ref "U6") (pin "4") (pinfunction "GNDI_4") (pintype "passive"))
      (node (ref "U7") (pin "4") (pinfunction "GNDI_4") (pintype "passive"))
      (node (ref "U8") (pin "4") (pinfunction "GNDI_4") (pintype "passive"))
      (node (ref "U9") (pin "4") (pinfunction "GNDI_4") (pintype "passive"))
      (node (ref "Y1") (pin "2") (pinfunction "2_2") (pintype "passive"))
      (node (ref "Y1") (pin "4") (pinfunction "4_4") (pintype "passive"))
    )
    (net (code "148") (name "Net-(C21-Pad1)") (class "Default")
      (node (ref "C21") (pin "1") (pinfunction "1_1") (pintype "passive"))
      (node (ref "D2") (pin "3") (pinfunction "3_3") (pintype "passive"))
    )
    (net (code "149") (name "Net-(C23-Pad1)") (class "Default")
      (node (ref "C23") (pin "1") (pinfunction "1_1") (pintype "passive"))
      (node (ref "D3") (pin "3") (pinfunction "3_3") (pintype "passive"))
    )
    (net (code "150") (name "Net-(C26-Pad1)") (class "Default")
      (node (ref "C26") (pin "1") (pinfunction "1_1") (pintype "passive"))
      (node (ref "D4") (pin "3") (pinfunction "3_3") (pintype "passive"))
    )
    (net (code "151") (name "Net-(C28-Pad1)") (class "Default")
      (node (ref "C28") (pin "1") (pinfunction "1_1") (pintype "passive"))
      (node (ref "D5") (pin "3") (pinfunction "3_3") (pintype "passive"))
    )
    (net (code "152") (name "Net-(C31-Pad1)") (class "Default")
      (node (ref "C31") (pin "1") (pinfunction "1_1") (pintype "passive"))
      (node (ref "D6") (pin "3") (pinfunction "3_3") (pintype "passive"))
    )
    (net (code "153") (name "Net-(C60-Pad1)") (class "Default")
      (node (ref "C60") (pin "1") (pinfunction "1_1") (pintype "passive"))
      (node (ref "L2") (pin "1") (pinfunction "1_1") (pintype "passive"))
      (node (ref "P4") (pin "17") (pinfunction "17_17") (pintype "passive"))
      (node (ref "P4") (pin "18") (pinfunction "18_18") (pintype "passive"))
    )
    (net (code "154") (name "Net-(D1-A)") (class "Default")
      (node (ref "D1") (pin "1") (pinfunction "A_1") (pintype "passive"))
      (node (ref "Q1") (pin "3") (pinfunction "D_3") (pintype "passive"))
    )
    (net (code "155") (name "Net-(D1-K)") (class "Default")
      (node (ref "D1") (pin "2") (pinfunction "K_2") (pintype "passive"))
      (node (ref "R12") (pin "2") (pinfunction "2_2") (pintype "passive"))
    )
    (net (code "156") (name "Net-(D7-K)") (class "Default")
      (node (ref "C36") (pin "1") (pinfunction "1_1") (pintype "passive"))
      (node (ref "D7") (pin "2") (pinfunction "K_2") (pintype "passive"))
      (node (ref "U6") (pin "14") (pinfunction "VDDA_14") (pintype "passive"))
    )
    (net (code "157") (name "Net-(D8-K)") (class "Default")
      (node (ref "C39") (pin "1") (pinfunction "1_1") (pintype "passive"))
      (node (ref "D8") (pin "2") (pinfunction "K_2") (pintype "passive"))
      (node (ref "U7") (pin "14") (pinfunction "VDDA_14") (pintype "passive"))
    )
    (net (code "158") (name "Net-(D9-K)") (class "Default")
      (node (ref "C42") (pin "1") (pinfunction "1_1") (pintype "passive"))
      (node (ref "D9") (pin "2") (pinfunction "K_2") (pintype "passive"))
      (node (ref "U8") (pin "14") (pinfunction "VDDA_14") (pintype "passive"))
    )
    (net (code "159") (name "Net-(D10-K)") (class "Default")
      (node (ref "C45") (pin "1") (pinfunction "1_1") (pintype "passive"))
      (node (ref "D10") (pin "2") (pinfunction "K_2") (pintype "passive"))
      (node (ref "U9") (pin "14") (pinfunction "VDDA_14") (pintype "passive"))
    )
    (net (code "160") (name "Net-(D12-PadA)") (class "Default")
      (node (ref "D12") (pin "A") (pinfunction "A_A") (pintype "passive"))
      (node (ref "P3") (pin "1") (pinfunction "1_1") (pintype "passive"))
      (node (ref "Q6") (pin "D") (pinfunction "D_D") (pintype "passive"))
    )
    (net (code "161") (name "Net-(D14-K)") (class "Default")
      (node (ref "D14") (pin "2") (pinfunction "K_2") (pintype "passive"))
      (node (ref "R52") (pin "2") (pinfunction "2_2") (pintype "passive"))
    )
    (net (code "162") (name "Net-(D15-K)") (class "Default")
      (node (ref "D15") (pin "2") (pinfunction "K_2") (pintype "passive"))
      (node (ref "R54") (pin "2") (pinfunction "2_2") (pintype "passive"))
    )
    (net (code "163") (name "Net-(D16-Pad1)") (class "Default")
      (node (ref "D16") (pin "1") (pinfunction "1_1") (pintype "passive"))
      (node (ref "R62") (pin "2") (pinfunction "2_2") (pintype "passive"))
    )
    (net (code "164") (name "Net-(D16-Pad3)") (class "Default")
      (node (ref "D16") (pin "3") (pinfunction "3_3") (pintype "passive"))
      (node (ref "R63") (pin "2") (pinfunction "2_2") (pintype "passive"))
    )
    (net (code "165") (name "Net-(D16-Pad4)") (class "Default")
      (node (ref "D16") (pin "4") (pinfunction "4_4") (pintype "passive"))
      (node (ref "R64") (pin "2") (pinfunction "2_2") (pintype "passive"))
    )
    (net (code "166") (name "Net-(D17-K)") (class "Default")
      (node (ref "D17") (pin "2") (pinfunction "K_2") (pintype "passive"))
      (node (ref "R66") (pin "2") (pinfunction "2_2") (pintype "passive"))
    )
    (net (code "167") (name "Net-(Q1-G)") (class "Default")
      (node (ref "Q1") (pin "1") (pinfunction "G_1") (pintype "passive"))
      (node (ref "R11") (pin "1") (pinfunction "1_1") (pintype "passive"))
    )
    (net (code "168") (name "Net-(Q2-G1)") (class "Default")
      (node (ref "Q2") (pin "1") (pinfunction "G1_1") (pintype "passive"))
      (node (ref "R37") (pin "2") (pinfunction "2_2") (pintype "passive"))
    )
    (net (code "169") (name "Net-(Q2-G2)") (class "Default")
      (node (ref "Q2") (pin "4") (pinfunction "G2_4") (pintype "passive"))
      (node (ref "R38") (pin "2") (pinfunction "2_2") (pintype "passive"))
    )
    (net (code "170") (name "Net-(Q3-G1)") (class "Default")
      (node (ref "Q3") (pin "1") (pinfunction "G1_1") (pintype "passive"))
      (node (ref "R41") (pin "2") (pinfunction "2_2") (pintype "passive"))
    )
    (net (code "171") (name "Net-(Q3-G2)") (class "Default")
      (node (ref "Q3") (pin "4") (pinfunction "G2_4") (pintype "passive"))
      (node (ref "R42") (pin "2") (pinfunction "2_2") (pintype "passive"))
    )
    (net (code "172") (name "Net-(Q4-G1)") (class "Default")
      (node (ref "Q4") (pin "1") (pinfunction "G1_1") (pintype "passive"))
      (node (ref "R45") (pin "2") (pinfunction "2_2") (pintype "passive"))
    )
    (net (code "173") (name "Net-(Q4-G2)") (class "Default")
      (node (ref "Q4") (pin "4") (pinfunction "G2_4") (pintype "passive"))
      (node (ref "R46") (pin "2") (pinfunction "2_2") (pintype "passive"))
    )
    (net (code "174") (name "Net-(Q5-G1)") (class "Default")
      (node (ref "Q5") (pin "1") (pinfunction "G1_1") (pintype "passive"))
      (node (ref "R49") (pin "2") (pinfunction "2_2") (pintype "passive"))
    )
    (net (code "175") (name "Net-(Q5-G2)") (class "Default")
      (node (ref "Q5") (pin "4") (pinfunction "G2_4") (pintype "passive"))
      (node (ref "R50") (pin "2") (pinfunction "2_2") (pintype "passive"))
    )
    (net (code "176") (name "Net-(Q6-PadG)") (class "Default")
      (node (ref "Q6") (pin "G") (pinfunction "G_G") (pintype "passive"))
      (node (ref "R67") (pin "1") (pinfunction "1_1") (pintype "passive"))
    )
    (net (code "177") (name "Net-(R58-Pad1)") (class "Default")
      (node (ref "R58") (pin "1") (pinfunction "1_1") (pintype "passive"))
      (node (ref "S2") (pin "2") (pinfunction "2_2") (pintype "passive"))
    )
    (net (code "178") (name "Net-(R59-Pad1)") (class "Default")
      (node (ref "R59") (pin "1") (pinfunction "1_1") (pintype "passive"))
      (node (ref "S3") (pin "2") (pinfunction "2_2") (pintype "passive"))
    )
    (net (code "179") (name "Net-(R60-Pad1)") (class "Default")
      (node (ref "R60") (pin "1") (pinfunction "1_1") (pintype "passive"))
      (node (ref "S4") (pin "2") (pinfunction "2_2") (pintype "passive"))
    )
    (net (code "180") (name "Net-(R61-Pad1)") (class "Default")
      (node (ref "R61") (pin "1") (pinfunction "1_1") (pintype "passive"))
      (node (ref "S5") (pin "2") (pinfunction "2_2") (pintype "passive"))
    )
    (net (code "181") (name "Net-(U3A-+IN_A)") (class "Default")
      (node (ref "R16") (pin "2") (pinfunction "2_2") (pintype "passive"))
      (node (ref "U3") (pin "3") (pinfunction "+IN_A_3") (pintype "input"))
    )
    (net (code "182") (name "Net-(U3A--IN_A)") (class "Default")
      (node (ref "R13") (pin "2") (pinfunction "2_2") (pintype "passive"))
      (node (ref "R14") (pin "1") (pinfunction "1_1") (pintype "passive"))
      (node (ref "U3") (pin "2") (pinfunction "-IN_A_2") (pintype "input"))
    )
    (net (code "183") (name "Net-(U3A-OUT_A)") (class "Default")
      (node (ref "C21") (pin "2") (pinfunction "2_2") (pintype "passive"))
      (node (ref "R14") (pin "2") (pinfunction "2_2") (pintype "passive"))
      (node (ref "U3") (pin "1") (pinfunction "OUT_A_1") (pintype "output"))
    )
    (net (code "184") (name "Net-(U3B-+IN_B)") (class "Default")
      (node (ref "R20") (pin "2") (pinfunction "2_2") (pintype "passive"))
      (node (ref "U3") (pin "5") (pinfunction "+IN_B_5") (pintype "input"))
    )
    (net (code "185") (name "Net-(U3B--IN_B)") (class "Default")
      (node (ref "R17") (pin "2") (pinfunction "2_2") (pintype "passive"))
      (node (ref "R18") (pin "1") (pinfunction "1_1") (pintype "passive"))
      (node (ref "U3") (pin "6") (pinfunction "-IN_B_6") (pintype "input"))
    )
    (net (code "186") (name "Net-(U3B-OUT_B)") (class "Default")
      (node (ref "C23") (pin "2") (pinfunction "2_2") (pintype "passive"))
      (node (ref "R18") (pin "2") (pinfunction "2_2") (pintype "passive"))
      (node (ref "U3") (pin "7") (pinfunction "OUT_B_7") (pintype "output"))
    )
    (net (code "187") (name "Net-(U4A-+IN_A)") (class "Default")
      (node (ref "R24") (pin "2") (pinfunction "2_2") (pintype "passive"))
      (node (ref "U4") (pin "3") (pinfunction "+IN_A_3") (pintype "input"))
    )
    (net (code "188") (name "Net-(U4A--IN_A)") (class "Default")
      (node (ref "R21") (pin "2") (pinfunction "2_2") (pintype "passive"))
      (node (ref "R22") (pin "1") (pinfunction "1_1") (pintype "passive"))
      (node (ref "U4") (pin "2") (pinfunction "-IN_A_2") (pintype "input"))
    )
    (net (code "189") (name "Net-(U4A-OUT_A)") (class "Default")
      (node (ref "C26") (pin "2") (pinfunction "2_2") (pintype "passive"))
      (node (ref "R22") (pin "2") (pinfunction "2_2") (pintype "passive"))
      (node (ref "U4") (pin "1") (pinfunction "OUT_A_1") (pintype "output"))
    )
    (net (code "190") (name "Net-(U4B-+IN_B)") (class "Default")
      (node (ref "R28") (pin "2") (pinfunction "2_2") (pintype "passive"))
      (node (ref "U4") (pin "5") (pinfunction "+IN_B_5") (pintype "input"))
    )
    (net (code "191") (name "Net-(U4B--IN_B)") (class "Default")
      (node (ref "R25") (pin "2") (pinfunction "2_2") (pintype "passive"))
      (node (ref "R26") (pin "1") (pinfunction "1_1") (pintype "passive"))
      (node (ref "U4") (pin "6") (pinfunction "-IN_B_6") (pintype "input"))
    )
    (net (code "192") (name "Net-(U4B-OUT_B)") (class "Default")
      (node (ref "C28") (pin "2") (pinfunction "2_2") (pintype "passive"))
      (node (ref "R26") (pin "2") (pinfunction "2_2") (pintype "passive"))
      (node (ref "U4") (pin "7") (pinfunction "OUT_B_7") (pintype "output"))
    )
    (net (code "193") (name "Net-(U5A-+IN_A)") (class "Default")
      (node (ref "C33") (pin "1") (pinfunction "1_1") (pintype "passive"))
      (node (ref "R33") (pin "2") (pinfunction "2_2") (pintype "passive"))
      (node (ref "R34") (pin "1") (pinfunction "1_1") (pintype "passive"))
      (node (ref "U5") (pin "3") (pinfunction "+IN_A_3") (pintype "input"))
    )
    (net (code "194") (name "Net-(U5B-+IN_B)") (class "Default")
      (node (ref "R32") (pin "2") (pinfunction "2_2") (pintype "passive"))
      (node (ref "U5") (pin "5") (pinfunction "+IN_B_5") (pintype "input"))
    )
    (net (code "195") (name "Net-(U5B--IN_B)") (class "Default")
      (node (ref "R29") (pin "2") (pinfunction "2_2") (pintype "passive"))
      (node (ref "R30") (pin "1") (pinfunction "1_1") (pintype "passive"))
      (node (ref "U5") (pin "6") (pinfunction "-IN_B_6") (pintype "input"))
    )
    (net (code "196") (name "Net-(U5B-OUT_B)") (class "Default")
      (node (ref "C31") (pin "2") (pinfunction "2_2") (pintype "passive"))
      (node (ref "R30") (pin "2") (pinfunction "2_2") (pintype "passive"))
      (node (ref "U5") (pin "7") (pinfunction "OUT_B_7") (pintype "output"))
    )
    (net (code "197") (name "Net-(U6-DT)") (class "Default")
      (node (ref "R36") (pin "2") (pinfunction "2_2") (pintype "passive"))
      (node (ref "U6") (pin "6") (pinfunction "DT_6") (pintype "passive"))
    )
    (net (code "198") (name "Net-(U7-DT)") (class "Default")
      (node (ref "R40") (pin "2") (pinfunction "2_2") (pintype "passive"))
      (node (ref "U7") (pin "6") (pinfunction "DT_6") (pintype "passive"))
    )
    (net (code "199") (name "Net-(U8-DT)") (class "Default")
      (node (ref "R44") (pin "2") (pinfunction "2_2") (pintype "passive"))
      (node (ref "U8") (pin "6") (pinfunction "DT_6") (pintype "passive"))
    )
    (net (code "200") (name "Net-(U9-DT)") (class "Default")
      (node (ref "R48") (pin "2") (pinfunction "2_2") (pintype "passive"))
      (node (ref "U9") (pin "6") (pinfunction "DT_6") (pintype "passive"))
    )
    (net (code "201") (name "Net-(U10-VIN)") (class "Default")
      (node (ref "C51") (pin "1") (pinfunction "1_1") (pintype "passive"))
      (node (ref "F1") (pin "2") (pinfunction "2_2") (pintype "passive"))
      (node (ref "U10") (pin "4") (pinfunction "VIN_4") (pintype "passive"))
    )
    (net (code "202") (name "Net-(U11-NR)") (class "Default")
      (node (ref "C56") (pin "2") (pinfunction "2_2") (pintype "passive"))
      (node (ref "U11") (pin "4") (pinfunction "NR_4") (pintype "passive"))
    )
    (net (code "203") (name "Net-(U12-NR)") (class "Default")
      (node (ref "C59") (pin "2") (pinfunction "2_2") (pintype "passive"))
      (node (ref "U12") (pin "4") (pinfunction "NR_4") (pintype "passive"))
    )
    (net (code "204") (name "Net-(U13-A)") (class "Default")
      (node (ref "R55") (pin "2") (pinfunction "2_2") (pintype "passive"))
      (node (ref "U13") (pin "1") (pinfunction "A_1") (pintype "passive"))
    )
    (net (code "205") (name "Net-(U13-C)") (class "Default")
      (node (ref "B1") (pin "2") (pinfunction "2_2") (pintype "passive"))
      (node (ref "U13") (pin "4") (pinfunction "C_4") (pintype "passive"))
    )
    (net (code "206") (name "PGND") (class "Default")
      (node (ref "C37") (pin "2") (pinfunction "2_2") (pintype "passive"))
      (node (ref "C40") (pin "2") (pinfunction "2_2") (pintype "passive"))
      (node (ref "C43") (pin "2") (pinfunction "2_2") (pintype "passive"))
      (node (ref "C46") (pin "2") (pinfunction "2_2") (pintype "passive"))
      (node (ref "C48") (pin "2") (pinfunction "2_2") (pintype "passive"))
      (node (ref "C49") (pin "2") (pinfunction "2_2") (pintype "passive"))
      (node (ref "C51") (pin "2") (pinfunction "2_2") (pintype "passive"))
      (node (ref "C52") (pin "2") (pinfunction "2_2") (pintype "passive"))
      (node (ref "C61") (pin "2") (pinfunction "2_2") (pintype "passive"))
      (node (ref "C68") (pin "2") (pinfunction "2_2") (pintype "passive"))
      (node (ref "C69") (pin "2") (pinfunction "2_2") (pintype "passive"))
      (node (ref "C70") (pin "2") (pinfunction "2_2") (pintype "passive"))
      (node (ref "C71") (pin "2") (pinfunction "2_2") (pintype "passive"))
      (node (ref "C72") (pin "2") (pinfunction "2_2") (pintype "passive"))
      (node (ref "C73") (pin "2") (pinfunction "2_2") (pintype "passive"))
      (node (ref "C74") (pin "2") (pinfunction "2_2") (pintype "passive"))
      (node (ref "C75") (pin "2") (pinfunction "2_2") (pintype "passive"))
      (node (ref "C76") (pin "2") (pinfunction "2_2") (pintype "passive"))
      (node (ref "C77") (pin "2") (pinfunction "2_2") (pintype "passive"))
      (node (ref "C79") (pin "2") (pinfunction "2_2") (pintype "passive"))
      (node (ref "C80") (pin "2") (pinfunction "2_2") (pintype "passive"))
      (node (ref "C81") (pin "2") (pinfunction "2_2") (pintype "passive"))
      (node (ref "C82") (pin "2") (pinfunction "2_2") (pintype "passive"))
      (node (ref "C83") (pin "2") (pinfunction "2_2") (pintype "passive"))
      (node (ref "C84") (pin "2") (pinfunction "2_2") (pintype "passive"))
      (node (ref "C85") (pin "2") (pinfunction "2_2") (pintype "passive"))
      (node (ref "D12") (pin "K") (pinfunction "K_K") (pintype "passive"))
      (node (ref "P3") (pin "2") (pinfunction "2_2") (pintype "passive"))
      (node (ref "Q2") (pin "2") (pinfunction "S2_2") (pintype "passive"))
      (node (ref "Q2") (pin "3") (pinfunction "S2_3") (pintype "passive"))
      (node (ref "Q3") (pin "2") (pinfunction "S2_2") (pintype "passive"))
      (node (ref "Q3") (pin "3") (pinfunction "S2_3") (pintype "passive"))
      (node (ref "Q4") (pin "2") (pinfunction "S2_2") (pintype "passive"))
      (node (ref "Q4") (pin "3") (pinfunction "S2_3") (pintype "passive"))
      (node (ref "Q5") (pin "2") (pinfunction "S2_2") (pintype "passive"))
      (node (ref "Q5") (pin "3") (pinfunction "S2_3") (pintype "passive"))
      (node (ref "R52") (pin "1") (pinfunction "1_1") (pintype "passive"))
      (node (ref "R67") (pin "2") (pinfunction "2_2") (pintype "passive"))
      (node (ref "U10") (pin "1") (pinfunction "GND_1") (pintype "passive"))
      (node (ref "U13") (pin "3") (pinfunction "E_3") (pintype "passive"))
      (node (ref "U6") (pin "8") (pinfunction "GNDB_8") (pintype "passive"))
      (node (ref "U7") (pin "8") (pinfunction "GNDB_8") (pintype "passive"))
      (node (ref "U8") (pin "8") (pinfunction "GNDB_8") (pintype "passive"))
      (node (ref "U9") (pin "8") (pinfunction "GNDB_8") (pintype "passive"))
    )
    (net (code "207") (name "VBAT") (class "Default")
      (node (ref "B1") (pin "1") (pinfunction "1_1") (pintype "passive"))
      (node (ref "C37") (pin "1") (pinfunction "1_1") (pintype "passive"))
      (node (ref "C40") (pin "1") (pinfunction "1_1") (pintype "passive"))
      (node (ref "C43") (pin "1") (pinfunction "1_1") (pintype "passive"))
      (node (ref "C46") (pin "1") (pinfunction "1_1") (pintype "passive"))
      (node (ref "C48") (pin "1") (pinfunction "1_1") (pintype "passive"))
      (node (ref "C49") (pin "1") (pinfunction "1_1") (pintype "passive"))
      (node (ref "C61") (pin "1") (pinfunction "1_1") (pintype "passive"))
      (node (ref "C68") (pin "1") (pinfunction "1_1") (pintype "passive"))
      (node (ref "C69") (pin "1") (pinfunction "1_1") (pintype "passive"))
      (node (ref "C70") (pin "1") (pinfunction "1_1") (pintype "passive"))
      (node (ref "C71") (pin "1") (pinfunction "1_1") (pintype "passive"))
      (node (ref "C72") (pin "1") (pinfunction "1_1") (pintype "passive"))
      (node (ref "C73") (pin "1") (pinfunction "1_1") (pintype "passive"))
      (node (ref "C74") (pin "1") (pinfunction "1_1") (pintype "passive"))
      (node (ref "C75") (pin "1") (pinfunction "1_1") (pintype "passive"))
      (node (ref "C76") (pin "1") (pinfunction "1_1") (pintype "passive"))
      (node (ref "C77") (pin "1") (pinfunction "1_1") (pintype "passive"))
      (node (ref "C79") (pin "1") (pinfunction "1_1") (pintype "passive"))
      (node (ref "C80") (pin "1") (pinfunction "1_1") (pintype "passive"))
      (node (ref "C81") (pin "1") (pinfunction "1_1") (pintype "passive"))
      (node (ref "C82") (pin "1") (pinfunction "1_1") (pintype "passive"))
      (node (ref "C83") (pin "1") (pinfunction "1_1") (pintype "passive"))
      (node (ref "C84") (pin "1") (pinfunction "1_1") (pintype "passive"))
      (node (ref "C85") (pin "1") (pinfunction "1_1") (pintype "passive"))
      (node (ref "D10") (pin "1") (pinfunction "A_1") (pintype "passive"))
      (node (ref "D14") (pin "1") (pinfunction "A_1") (pintype "passive"))
      (node (ref "D7") (pin "1") (pinfunction "A_1") (pintype "passive"))
      (node (ref "D8") (pin "1") (pinfunction "A_1") (pintype "passive"))
      (node (ref "D9") (pin "1") (pinfunction "A_1") (pintype "passive"))
      (node (ref "F1") (pin "1") (pinfunction "1_1") (pintype "passive"))
      (node (ref "Q2") (pin "6") (pinfunction "D1_6") (pintype "passive"))
      (node (ref "Q3") (pin "6") (pinfunction "D1_6") (pintype "passive"))
      (node (ref "Q4") (pin "6") (pinfunction "D1_6") (pintype "passive"))
      (node (ref "Q5") (pin "6") (pinfunction "D1_6") (pintype "passive"))
      (node (ref "Q6") (pin "S") (pinfunction "S_S") (pintype "passive"))
      (node (ref "U6") (pin "10") (pinfunction "VDDB_10") (pintype "passive"))
      (node (ref "U7") (pin "10") (pinfunction "VDDB_10") (pintype "passive"))
      (node (ref "U8") (pin "10") (pinfunction "VDDB_10") (pintype "passive"))
      (node (ref "U9") (pin "10") (pinfunction "VDDB_10") (pintype "passive"))
    )
    (net (code "208") (name "VCC_3V3_ISOL") (class "Default")
      (node (ref "C57") (pin "1") (pinfunction "1_1") (pintype "passive"))
      (node (ref "C62") (pin "1") (pinfunction "1_1") (pintype "passive"))
      (node (ref "C63") (pin "1") (pinfunction "1_1") (pintype "passive"))
      (node (ref "C64") (pin "1") (pinfunction "1_1") (pintype "passive"))
      (node (ref "C65") (pin "1") (pinfunction "1_1") (pintype "passive"))
      (node (ref "C66") (pin "1") (pinfunction "1_1") (pintype "passive"))
      (node (ref "C67") (pin "1") (pinfunction "1_1") (pintype "passive"))
      (node (ref "L2") (pin "2") (pinfunction "2_2") (pintype "passive"))
      (node (ref "P5") (pin "5") (pinfunction "5_5") (pintype "passive"))
      (node (ref "P6") (pin "5") (pinfunction "5_5") (pintype "passive"))
      (node (ref "P7") (pin "1") (pinfunction "1_1") (pintype "passive"))
      (node (ref "P8") (pin "2") (pinfunction "2_2") (pintype "passive"))
      (node (ref "P9") (pin "3") (pinfunction "3_3") (pintype "passive"))
      (node (ref "U12") (pin "5") (pinfunction "OUT_5") (pintype "power_in"))
    )
    (net (code "209") (name "VCC_5V_ISOL") (class "Default")
      (node (ref "C50") (pin "1") (pinfunction "1_1") (pintype "passive"))
      (node (ref "C55") (pin "1") (pinfunction "1_1") (pintype "passive"))
      (node (ref "C58") (pin "1") (pinfunction "1_1") (pintype "passive"))
      (node (ref "C90") (pin "1") (pinfunction "1_1") (pintype "passive"))
      (node (ref "C91") (pin "1") (pinfunction "1_1") (pintype "passive"))
      (node (ref "D15") (pin "1") (pinfunction "A_1") (pintype "passive"))
      (node (ref "P10") (pin "3") (pinfunction "3_3") (pintype "passive"))
      (node (ref "P11") (pin "1") (pinfunction "1_1") (pintype "passive"))
      (node (ref "R53") (pin "2") (pinfunction "2_2") (pintype "passive"))
      (node (ref "R65") (pin "1") (pinfunction "1_1") (pintype "passive"))
      (node (ref "U10") (pin "5") (pinfunction "+Vo_5") (pintype "passive"))
      (node (ref "U11") (pin "1") (pinfunction "IN_1") (pintype "power_in"))
      (node (ref "U12") (pin "1") (pinfunction "IN_1") (pintype "power_in"))
    )
    (net (code "210") (name "VCC_Core_1V3") (class "Default")
      (node (ref "C11") (pin "1") (pinfunction "1_1") (pintype "passive"))
      (node (ref "C5") (pin "1") (pinfunction "1_1") (pintype "passive"))
      (node (ref "C6") (pin "1") (pinfunction "1_1") (pintype "passive"))
      (node (ref "C7") (pin "1") (pinfunction "1_1") (pintype "passive"))
      (node (ref "C8") (pin "1") (pinfunction "1_1") (pintype "passive"))
      (node (ref "U1") (pin "10") (pinfunction "VDD/VDDSB_10") (pintype "power_in"))
      (node (ref "U1") (pin "22") (pinfunction "VDD_22") (pintype "power_in"))
      (node (ref "U1") (pin "58") (pinfunction "VDD_58") (pintype "power_in"))
      (node (ref "U1") (pin "79") (pinfunction "VDD_79") (pintype "power_in"))
      (node (ref "U1") (pin "99") (pinfunction "VDD_99") (pintype "power_in"))
      (node (ref "U2") (pin "2") (pinfunction "2_2") (pintype "passive"))
    )
    (net (code "211") (name "unconnected-(P1-Pad1)") (class "Default")
      (node (ref "P1") (pin "1") (pinfunction "1_1") (pintype "passive+no_connect"))
    )
    (net (code "212") (name "unconnected-(P4-Pad5)") (class "Default")
      (node (ref "P4") (pin "5") (pinfunction "5_5") (pintype "passive+no_connect"))
    )
    (net (code "213") (name "unconnected-(P5-Pad1)") (class "Default")
      (node (ref "P5") (pin "1") (pinfunction "1_1") (pintype "passive+no_connect"))
    )
    (net (code "214") (name "unconnected-(P5-Pad2)") (class "Default")
      (node (ref "P5") (pin "2") (pinfunction "2_2") (pintype "passive+no_connect"))
    )
    (net (code "215") (name "unconnected-(P6-Pad1)") (class "Default")
      (node (ref "P6") (pin "1") (pinfunction "1_1") (pintype "passive+no_connect"))
    )
    (net (code "216") (name "unconnected-(P6-Pad2)") (class "Default")
      (node (ref "P6") (pin "2") (pinfunction "2_2") (pintype "passive+no_connect"))
    )
    (net (code "217") (name "unconnected-(U1A-VGATE1P-Pad71)") (class "Default")
      (node (ref "U1") (pin "71") (pinfunction "VGATE1P_71") (pintype "output+no_connect"))
    )
    (net (code "218") (name "unconnected-(U1B-AN5-Pad52)") (class "Default")
      (node (ref "U1") (pin "52") (pinfunction "AN5_52") (pintype "input+no_connect"))
    )
    (net (code "219") (name "unconnected-(U1B-AN6-Pad51)") (class "Default")
      (node (ref "U1") (pin "51") (pinfunction "AN6_51") (pintype "input+no_connect"))
    )
    (net (code "220") (name "unconnected-(U1B-AN7-Pad50)") (class "Default")
      (node (ref "U1") (pin "50") (pinfunction "AN7_50") (pintype "input+no_connect"))
    )
    (net (code "221") (name "unconnected-(U1B-AN8-Pad49)") (class "Default")
      (node (ref "U1") (pin "49") (pinfunction "AN8_49") (pintype "input+no_connect"))
    )
    (net (code "222") (name "unconnected-(U1B-AN10-Pad48)") (class "Default")
      (node (ref "U1") (pin "48") (pinfunction "AN10_48") (pintype "input+no_connect"))
    )
    (net (code "223") (name "unconnected-(U1B-AN11-Pad47)") (class "Default")
      (node (ref "U1") (pin "47") (pinfunction "AN11_47") (pintype "input+no_connect"))
    )
    (net (code "224") (name "unconnected-(U1B-AN12-Pad46)") (class "Default")
      (node (ref "U1") (pin "46") (pinfunction "AN12_46") (pintype "input+no_connect"))
    )
    (net (code "225") (name "unconnected-(U1B-AN13-Pad45)") (class "Default")
      (node (ref "U1") (pin "45") (pinfunction "AN13_45") (pintype "input+no_connect"))
    )
    (net (code "226") (name "unconnected-(U1B-AN16-Pad40)") (class "Default")
      (node (ref "U1") (pin "40") (pinfunction "AN16_40") (pintype "input+no_connect"))
    )
    (net (code "227") (name "unconnected-(U1B-AN17-Pad39)") (class "Default")
      (node (ref "U1") (pin "39") (pinfunction "AN17_39") (pintype "input+no_connect"))
    )
    (net (code "228") (name "unconnected-(U1B-AN20-Pad38)") (class "Default")
      (node (ref "U1") (pin "38") (pinfunction "AN20_38") (pintype "input+no_connect"))
    )
    (net (code "229") (name "unconnected-(U1B-AN21-Pad37)") (class "Default")
      (node (ref "U1") (pin "37") (pinfunction "AN21_37") (pintype "input+no_connect"))
    )
    (net (code "230") (name "unconnected-(U1B-AN24-Pad36)") (class "Default")
      (node (ref "U1") (pin "36") (pinfunction "AN24_36") (pintype "input+no_connect"))
    )
    (net (code "231") (name "unconnected-(U1B-AN25-Pad35)") (class "Default")
      (node (ref "U1") (pin "35") (pinfunction "AN25_35") (pintype "input+no_connect"))
    )
    (net (code "232") (name "unconnected-(U1B-AN35-Pad34)") (class "Default")
      (node (ref "U1") (pin "34") (pinfunction "AN35_34") (pintype "input+no_connect"))
    )
    (net (code "233") (name "unconnected-(U1B-AN36-Pad33)") (class "Default")
      (node (ref "U1") (pin "33") (pinfunction "AN36_33") (pintype "input+no_connect"))
    )
    (net (code "234") (name "unconnected-(U1B-AN37-Pad32)") (class "Default")
      (node (ref "U1") (pin "32") (pinfunction "AN37_32") (pintype "input+no_connect"))
    )
    (net (code "235") (name "unconnected-(U1B-AN38-Pad31)") (class "Default")
      (node (ref "U1") (pin "31") (pinfunction "AN38_31") (pintype "input+no_connect"))
    )
    (net (code "236") (name "unconnected-(U1B-AN39-Pad30)") (class "Default")
      (node (ref "U1") (pin "30") (pinfunction "AN39_30") (pintype "input+no_connect"))
    )
    (net (code "237") (name "unconnected-(U1B-AN44-Pad29)") (class "Default")
      (node (ref "U1") (pin "29") (pinfunction "AN44_29") (pintype "input+no_connect"))
    )
    (net (code "238") (name "unconnected-(U1B-AN45-Pad28)") (class "Default")
      (node (ref "U1") (pin "28") (pinfunction "AN45_28") (pintype "input+no_connect"))
    )
    (net (code "239") (name "unconnected-(U1B-AN46-Pad27)") (class "Default")
      (node (ref "U1") (pin "27") (pinfunction "AN46_27") (pintype "input+no_connect"))
    )
    (net (code "240") (name "unconnected-(U1B-AN47-Pad26)") (class "Default")
      (node (ref "U1") (pin "26") (pinfunction "AN47_26") (pintype "input+no_connect"))
    )
    (net (code "241") (name "unconnected-(U1B-AN48-Pad25)") (class "Default")
      (node (ref "U1") (pin "25") (pinfunction "AN48_25") (pintype "input+no_connect"))
    )
    (net (code "242") (name "unconnected-(U1B-AN49-Pad24)") (class "Default")
      (node (ref "U1") (pin "24") (pinfunction "AN49_24") (pintype "input+no_connect"))
    )
    (net (code "243") (name "unconnected-(U1C-P00_8-Pad19)") (class "Default")
      (node (ref "U1") (pin "19") (pinfunction "P00_8_19") (pintype "bidirectional+no_connect"))
    )
    (net (code "244") (name "unconnected-(U1C-P00_9-Pad20)") (class "Default")
      (node (ref "U1") (pin "20") (pinfunction "P00_9_20") (pintype "bidirectional+no_connect"))
    )
    (net (code "245") (name "unconnected-(U1C-P00_12-Pad21)") (class "Default")
      (node (ref "U1") (pin "21") (pinfunction "P00_12_21") (pintype "bidirectional+no_connect"))
    )
    (net (code "246") (name "unconnected-(U1C-P02_6-Pad7)") (class "Default")
      (node (ref "U1") (pin "7") (pinfunction "P02_6_7") (pintype "bidirectional+no_connect"))
    )
    (net (code "247") (name "unconnected-(U1C-P02_7-Pad8)") (class "Default")
      (node (ref "U1") (pin "8") (pinfunction "P02_7_8") (pintype "bidirectional+no_connect"))
    )
    (net (code "248") (name "unconnected-(U1C-P02_8-Pad9)") (class "Default")
      (node (ref "U1") (pin "9") (pinfunction "P02_8_9") (pintype "bidirectional+no_connect"))
    )
    (net (code "249") (name "unconnected-(U1C-P10_1-Pad140)") (class "Default")
      (node (ref "U1") (pin "140") (pinfunction "P10_1_140") (pintype "bidirectional+no_connect"))
    )
    (net (code "250") (name "unconnected-(U1C-P10_2-Pad141)") (class "Default")
      (node (ref "U1") (pin "141") (pinfunction "P10_2_141") (pintype "bidirectional+no_connect"))
    )
    (net (code "251") (name "unconnected-(U1C-P10_3-Pad142)") (class "Default")
      (node (ref "U1") (pin "142") (pinfunction "P10_3_142") (pintype "bidirectional+no_connect"))
    )
    (net (code "252") (name "unconnected-(U1C-P11_11-Pad138)") (class "Default")
      (node (ref "U1") (pin "138") (pinfunction "P11_11_138") (pintype "bidirectional+no_connect"))
    )
    (net (code "253") (name "unconnected-(U1C-P11_12-Pad139)") (class "Default")
      (node (ref "U1") (pin "139") (pinfunction "P11_12_139") (pintype "bidirectional+no_connect"))
    )
    (net (code "254") (name "unconnected-(U1C-P14_0-Pad118)") (class "Default")
      (node (ref "U1") (pin "118") (pinfunction "P14_0_118") (pintype "bidirectional+no_connect"))
    )
    (net (code "255") (name "unconnected-(U1C-P14_1-Pad119)") (class "Default")
      (node (ref "U1") (pin "119") (pinfunction "P14_1_119") (pintype "bidirectional+no_connect"))
    )
    (net (code "256") (name "unconnected-(U1D-P15_3-Pad112)") (class "Default")
      (node (ref "U1") (pin "112") (pinfunction "P15_3_112") (pintype "bidirectional+no_connect"))
    )
    (net (code "257") (name "unconnected-(U1D-P15_4-Pad113)") (class "Default")
      (node (ref "U1") (pin "113") (pinfunction "P15_4_113") (pintype "bidirectional+no_connect"))
    )
    (net (code "258") (name "unconnected-(U1D-P15_5-Pad114)") (class "Default")
      (node (ref "U1") (pin "114") (pinfunction "P15_5_114") (pintype "bidirectional+no_connect"))
    )
    (net (code "259") (name "unconnected-(U1D-P15_8-Pad117)") (class "Default")
      (node (ref "U1") (pin "117") (pinfunction "P15_8_117") (pintype "bidirectional+no_connect"))
    )
    (net (code "260") (name "unconnected-(U1D-P20_6-Pad100)") (class "Default")
      (node (ref "U1") (pin "100") (pinfunction "P20_6_100") (pintype "bidirectional+no_connect"))
    )
    (net (code "261") (name "unconnected-(U1D-P20_7-Pad101)") (class "Default")
      (node (ref "U1") (pin "101") (pinfunction "P20_7_101") (pintype "bidirectional+no_connect"))
    )
    (net (code "262") (name "unconnected-(U1D-P20_8-Pad102)") (class "Default")
      (node (ref "U1") (pin "102") (pinfunction "P20_8_102") (pintype "bidirectional+no_connect"))
    )
    (net (code "263") (name "unconnected-(U1D-P20_9-Pad103)") (class "Default")
      (node (ref "U1") (pin "103") (pinfunction "P20_9_103") (pintype "bidirectional+no_connect"))
    )
    (net (code "264") (name "unconnected-(U1D-P20_10-Pad104)") (class "Default")
      (node (ref "U1") (pin "104") (pinfunction "P20_10_104") (pintype "bidirectional+no_connect"))
    )
    (net (code "265") (name "unconnected-(U1D-P20_11-Pad105)") (class "Default")
      (node (ref "U1") (pin "105") (pinfunction "P20_11_105") (pintype "bidirectional+no_connect"))
    )
    (net (code "266") (name "unconnected-(U1D-P20_12-Pad106)") (class "Default")
      (node (ref "U1") (pin "106") (pinfunction "P20_12_106") (pintype "bidirectional+no_connect"))
    )
    (net (code "267") (name "unconnected-(U1D-P20_13-Pad107)") (class "Default")
      (node (ref "U1") (pin "107") (pinfunction "P20_13_107") (pintype "bidirectional+no_connect"))
    )
    (net (code "268") (name "unconnected-(U1D-P20_14-Pad108)") (class "Default")
      (node (ref "U1") (pin "108") (pinfunction "P20_14_108") (pintype "bidirectional+no_connect"))
    )
    (net (code "269") (name "unconnected-(U1D-P21_6{slash}TDI-Pad88)") (class "Default")
      (node (ref "U1") (pin "88") (pinfunction "P21_6/TDI_88") (pintype "bidirectional+no_connect"))
    )
    (net (code "270") (name "unconnected-(U1D-P22_0-Pad74)") (class "Default")
      (node (ref "U1") (pin "74") (pinfunction "P22_0_74") (pintype "bidirectional+no_connect"))
    )
    (net (code "271") (name "unconnected-(U1D-P22_1-Pad75)") (class "Default")
      (node (ref "U1") (pin "75") (pinfunction "P22_1_75") (pintype "bidirectional+no_connect"))
    )
    (net (code "272") (name "unconnected-(U1D-P22_2-Pad76)") (class "Default")
      (node (ref "U1") (pin "76") (pinfunction "P22_2_76") (pintype "bidirectional+no_connect"))
    )
    (net (code "273") (name "unconnected-(U1D-P22_3-Pad77)") (class "Default")
      (node (ref "U1") (pin "77") (pinfunction "P22_3_77") (pintype "bidirectional+no_connect"))
    )
    (net (code "274") (name "unconnected-(U1D-P23_1-Pad73)") (class "Default")
      (node (ref "U1") (pin "73") (pinfunction "P23_1_73") (pintype "bidirectional+no_connect"))
    )
    (net (code "275") (name "unconnected-(U1D-P32_0{slash}VGATE1N-Pad70)") (class "Default")
      (node (ref "U1") (pin "70") (pinfunction "P32_0/VGATE1N_70") (pintype "bidirectional+no_connect"))
    )
    (net (code "276") (name "unconnected-(U1D-P32_4-Pad72)") (class "Default")
      (node (ref "U1") (pin "72") (pinfunction "P32_4_72") (pintype "bidirectional+no_connect"))
    )
    (net (code "277") (name "unconnected-(U1D-P33_4-Pad60)") (class "Default")
      (node (ref "U1") (pin "60") (pinfunction "P33_4_60") (pintype "bidirectional+no_connect"))
    )
    (net (code "278") (name "unconnected-(U1D-P33_5-Pad61)") (class "Default")
      (node (ref "U1") (pin "61") (pinfunction "P33_5_61") (pintype "bidirectional+no_connect"))
    )
    (net (code "279") (name "unconnected-(U1D-P33_10-Pad66)") (class "Default")
      (node (ref "U1") (pin "66") (pinfunction "P33_10_66") (pintype "bidirectional+no_connect"))
    )
    (net (code "280") (name "unconnected-(U1D-P33_11-Pad67)") (class "Default")
      (node (ref "U1") (pin "67") (pinfunction "P33_11_67") (pintype "bidirectional+no_connect"))
    )
    (net (code "281") (name "unconnected-(U3B-+V-Pad8)") (class "Default")
      (node (ref "U3") (pin "8") (pinfunction "+V_8") (pintype "power_in+no_connect"))
    )
    (net (code "282") (name "unconnected-(U3B--V-Pad4)") (class "Default")
      (node (ref "U3") (pin "4") (pinfunction "-V_4") (pintype "power_in+no_connect"))
    )
    (net (code "283") (name "unconnected-(U4B-+V-Pad8)") (class "Default")
      (node (ref "U4") (pin "8") (pinfunction "+V_8") (pintype "power_in+no_connect"))
    )
    (net (code "284") (name "unconnected-(U4B--V-Pad4)") (class "Default")
      (node (ref "U4") (pin "4") (pinfunction "-V_4") (pintype "power_in+no_connect"))
    )
    (net (code "285") (name "unconnected-(U5A-+V-Pad8)") (class "Default")
      (node (ref "U5") (pin "8") (pinfunction "+V_8") (pintype "power_in+no_connect"))
    )
    (net (code "286") (name "unconnected-(U5A--V-Pad4)") (class "Default")
      (node (ref "U5") (pin "4") (pinfunction "-V_4") (pintype "power_in+no_connect"))
    )
    (net (code "287") (name "unconnected-(U6-NC-Pad1)") (class "Default")
      (node (ref "U6") (pin "1") (pinfunction "NC_1") (pintype "passive+no_connect"))
    )
    (net (code "288") (name "unconnected-(U6-NC-Pad3)") (class "Default")
      (node (ref "U6") (pin "3") (pinfunction "NC_3") (pintype "passive"))
    )
    (net (code "289") (name "unconnected-(U6-NC-Pad11)") (class "Default")
      (node (ref "U6") (pin "11") (pinfunction "NC_11") (pintype "passive"))
    )
    (net (code "290") (name "unconnected-(U7-NC-Pad1)") (class "Default")
      (node (ref "U7") (pin "1") (pinfunction "NC_1") (pintype "passive+no_connect"))
    )
    (net (code "291") (name "unconnected-(U7-NC-Pad3)") (class "Default")
      (node (ref "U7") (pin "3") (pinfunction "NC_3") (pintype "passive"))
    )
    (net (code "292") (name "unconnected-(U7-NC-Pad11)") (class "Default")
      (node (ref "U7") (pin "11") (pinfunction "NC_11") (pintype "passive"))
    )
    (net (code "293") (name "unconnected-(U8-NC-Pad1)") (class "Default")
      (node (ref "U8") (pin "1") (pinfunction "NC_1") (pintype "passive+no_connect"))
    )
    (net (code "294") (name "unconnected-(U8-NC-Pad3)") (class "Default")
      (node (ref "U8") (pin "3") (pinfunction "NC_3") (pintype "passive"))
    )
    (net (code "295") (name "unconnected-(U8-NC-Pad11)") (class "Default")
      (node (ref "U8") (pin "11") (pinfunction "NC_11") (pintype "passive"))
    )
    (net (code "296") (name "unconnected-(U9-NC-Pad1)") (class "Default")
      (node (ref "U9") (pin "1") (pinfunction "NC_1") (pintype "passive+no_connect"))
    )
    (net (code "297") (name "unconnected-(U9-NC-Pad3)") (class "Default")
      (node (ref "U9") (pin "3") (pinfunction "NC_3") (pintype "passive"))
    )
    (net (code "298") (name "unconnected-(U9-NC-Pad11)") (class "Default")
      (node (ref "U9") (pin "11") (pinfunction "NC_11") (pintype "passive"))
    )
    (net (code "299") (name "unconnected-(U10-NC-Pad6)") (class "Default")
      (node (ref "U10") (pin "6") (pinfunction "NC_6") (pintype "passive+no_connect"))
    )
  )
)
